# board2eco.net
KiCad netlist of a schematic drawn in EAGLE
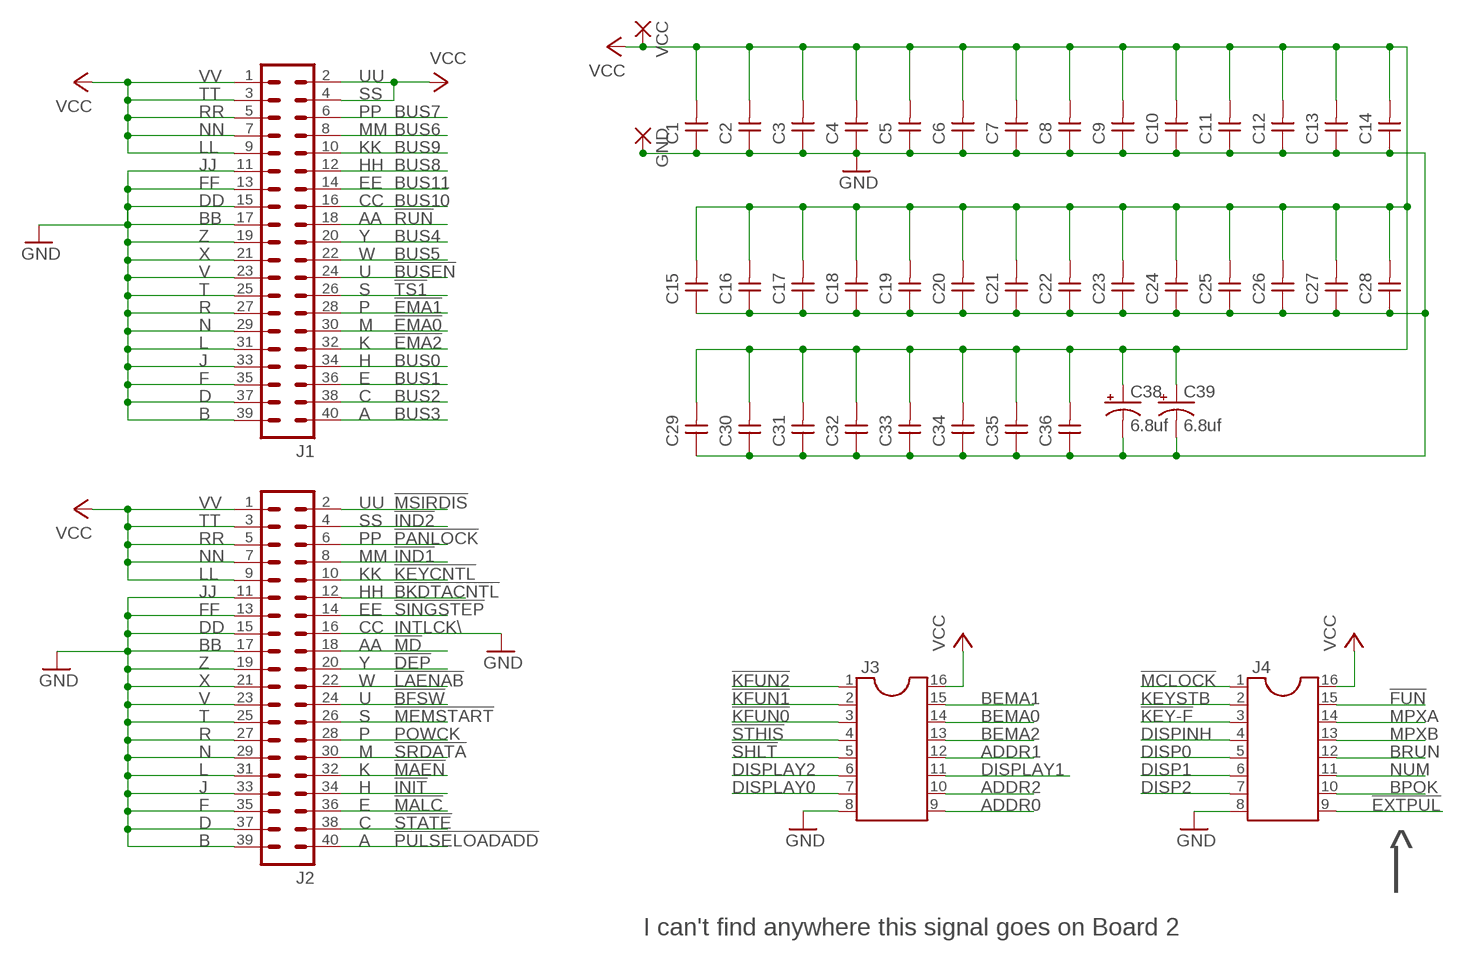
[diagram p0: schematic, sheet 1]
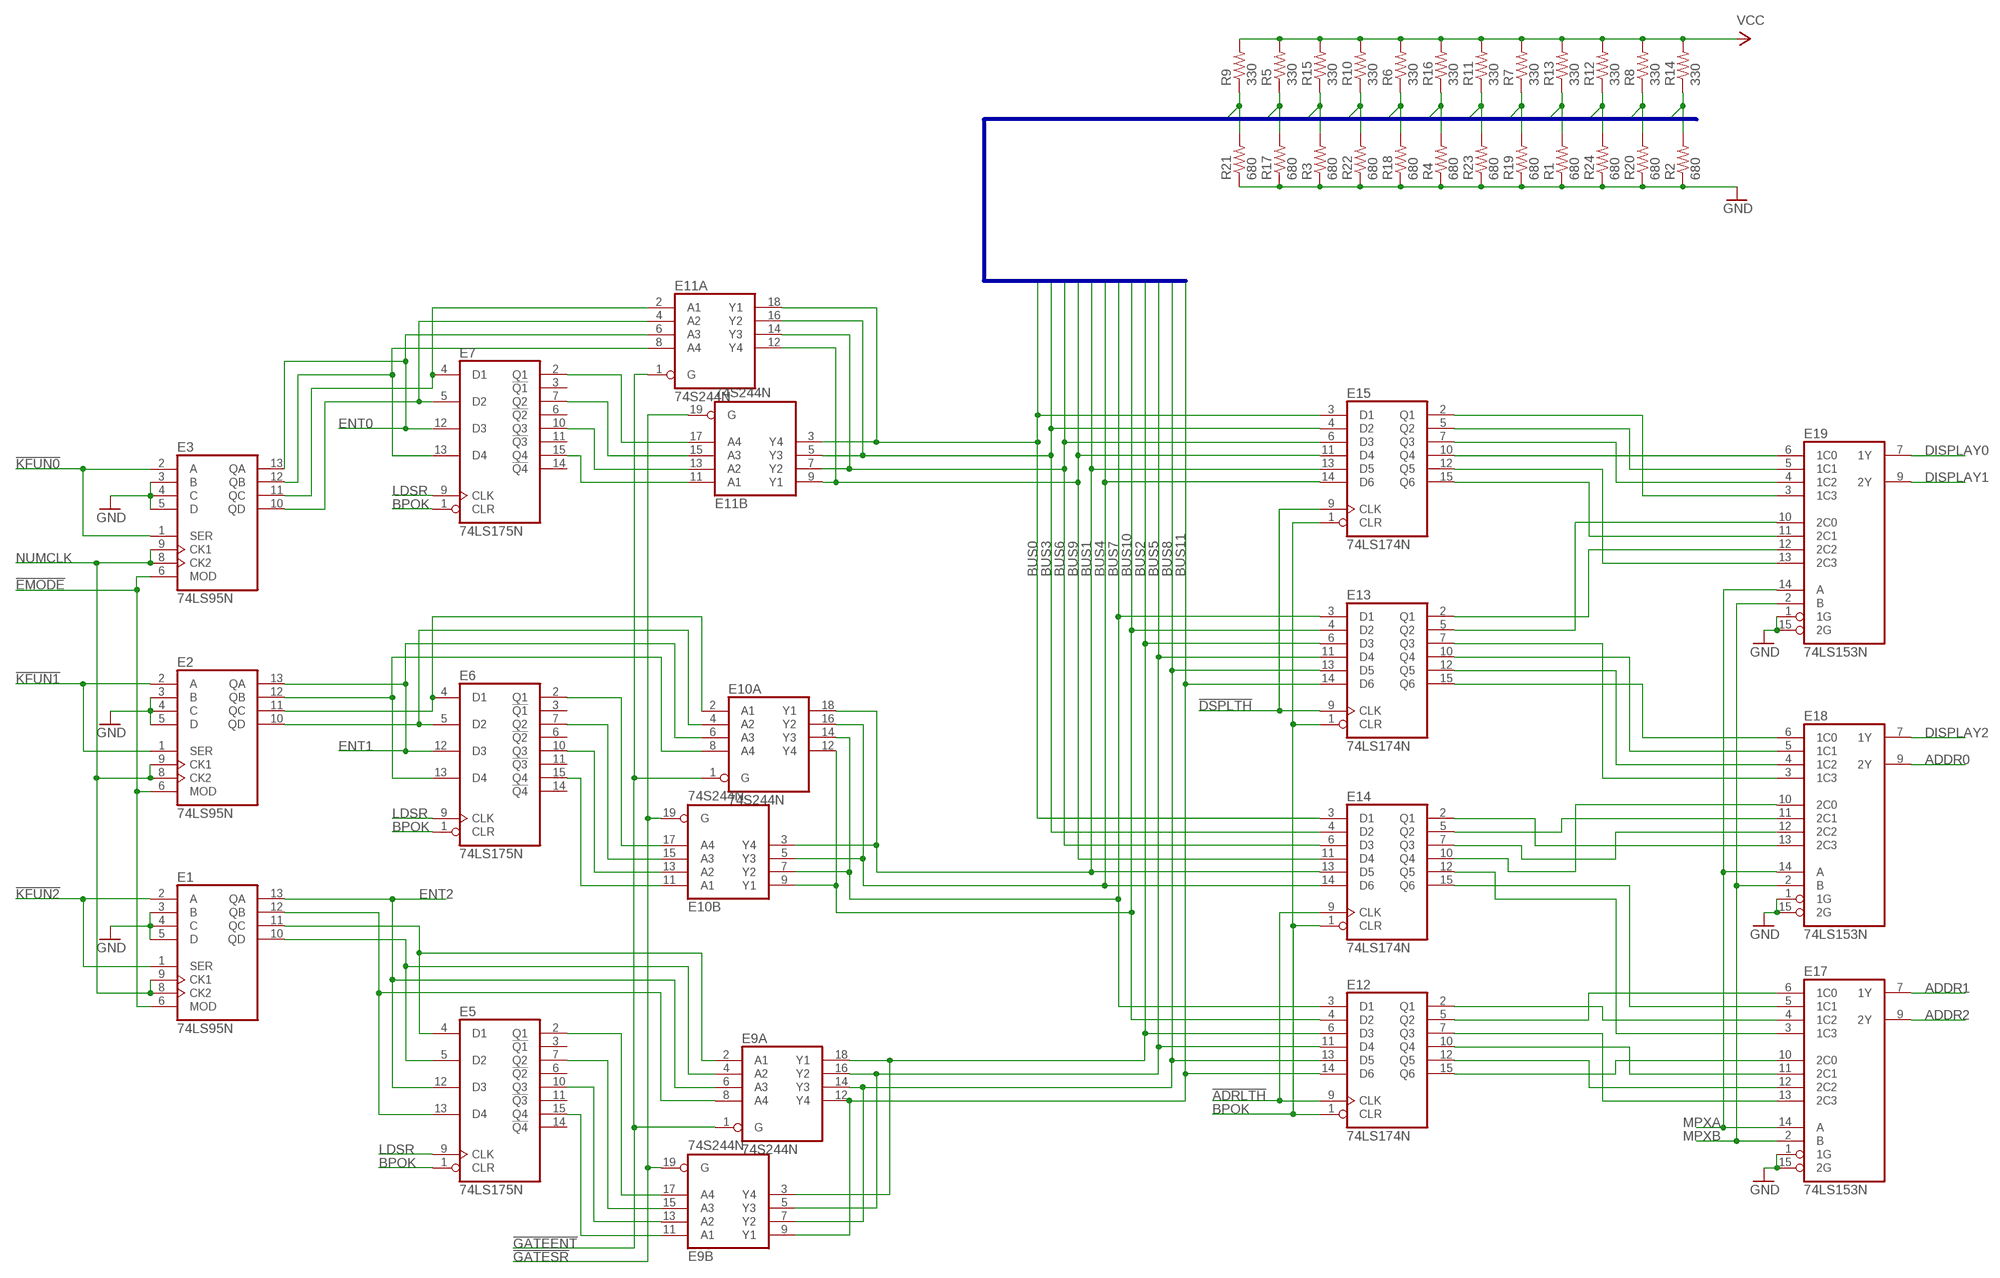
[diagram p1: schematic, sheet 2]
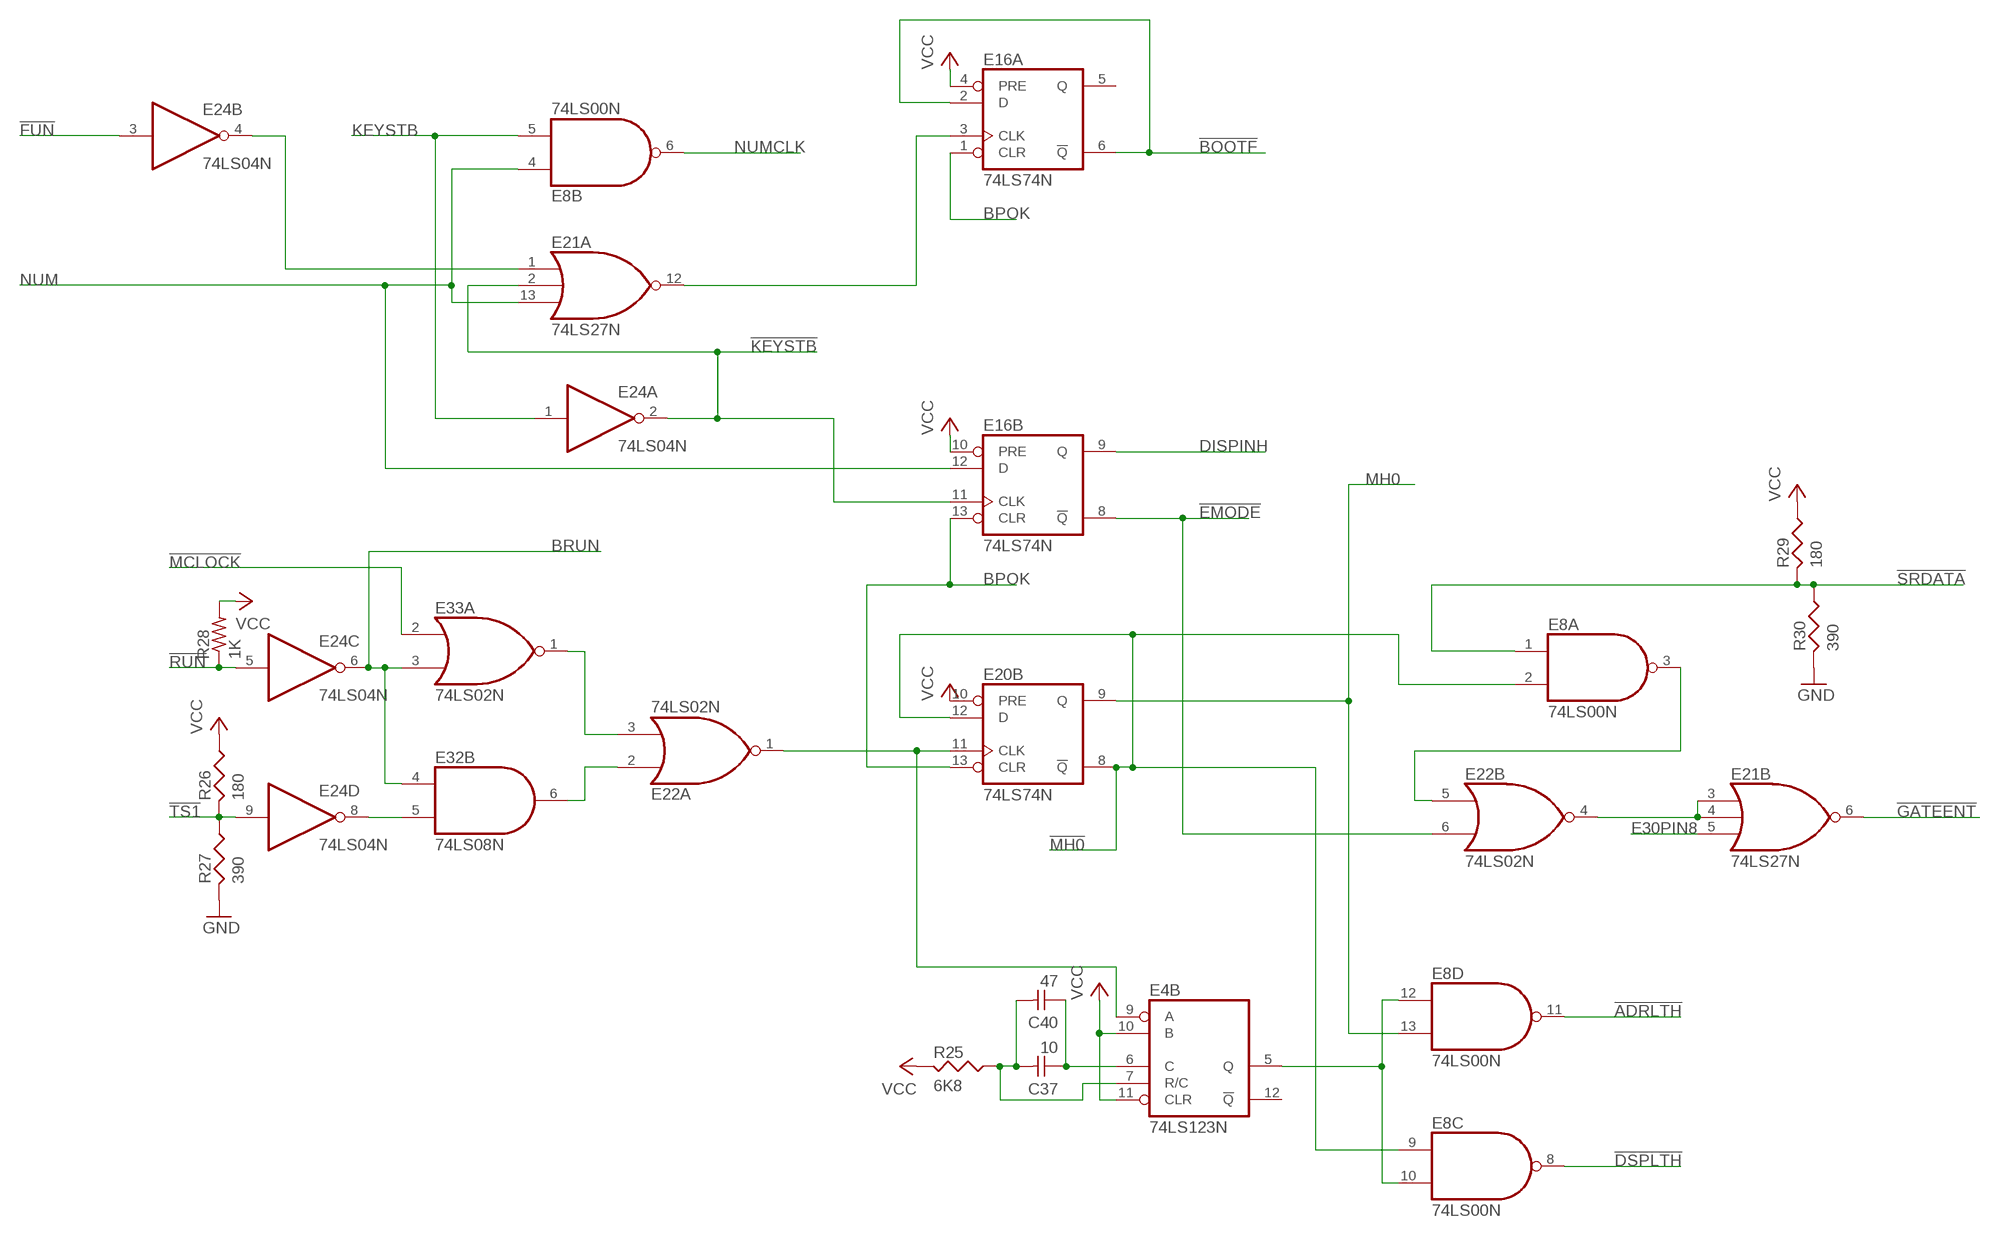
[diagram p2: schematic, sheet 3]
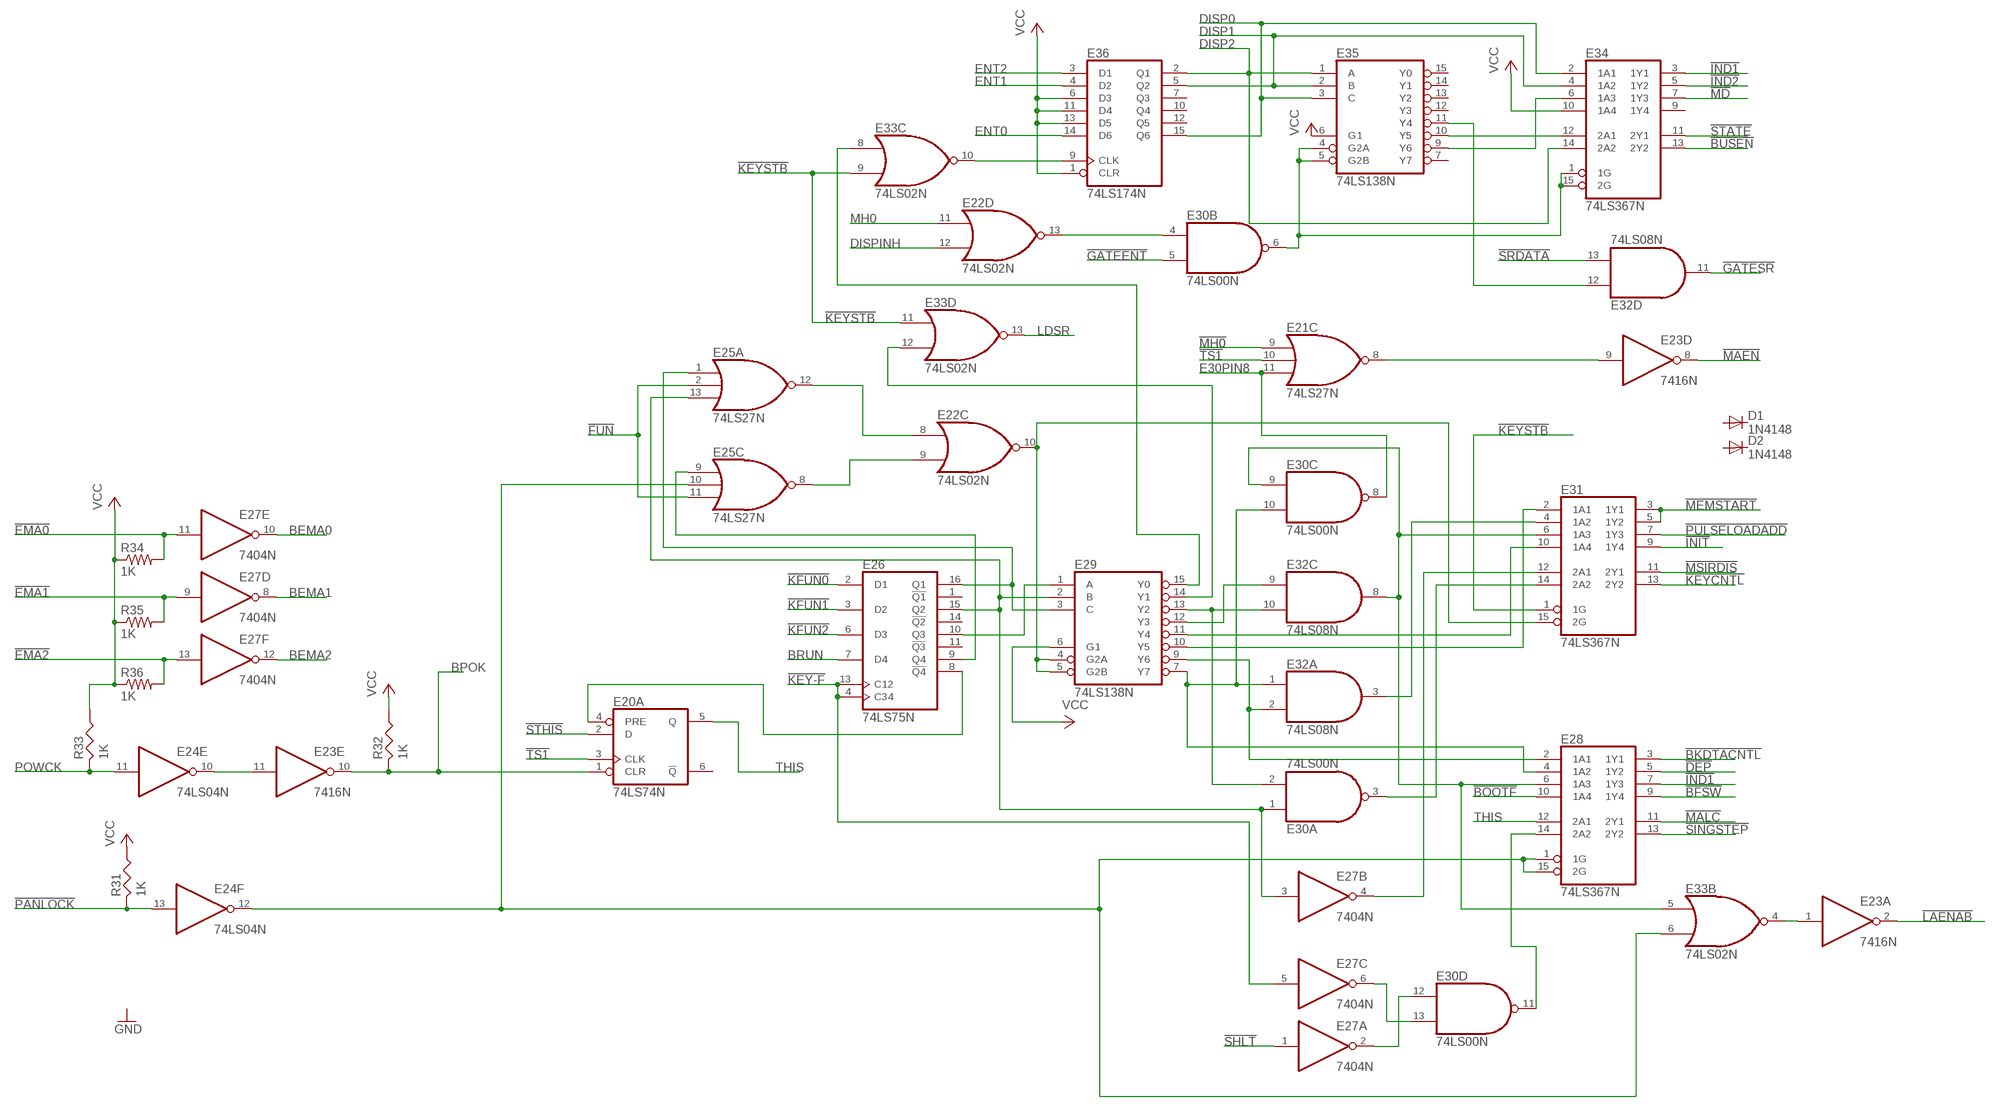
[diagram p3: schematic, sheet 4]

(export (version "E")
  (design (tool "Eeschema 10.0.6"))
  (components
    (comp (ref "E1")
      (value "74LS95N")
      (footprint "eagle-import:DIL14")
      (libsource (lib "eagle-import") (part "7495NLS"))
    )
    (comp (ref "E2")
      (value "74LS95N")
      (footprint "eagle-import:DIL14")
      (libsource (lib "eagle-import") (part "7495NLS"))
    )
    (comp (ref "E3")
      (value "74LS95N")
      (footprint "eagle-import:DIL14")
      (libsource (lib "eagle-import") (part "7495NLS"))
    )
    (comp (ref "E5")
      (value "74LS175N")
      (footprint "eagle-import:DIL16")
      (libsource (lib "eagle-import") (part "74175NLS"))
    )
    (comp (ref "E6")
      (value "74LS175N")
      (footprint "eagle-import:DIL16")
      (libsource (lib "eagle-import") (part "74175NLS"))
    )
    (comp (ref "E7")
      (value "74LS175N")
      (footprint "eagle-import:DIL16")
      (libsource (lib "eagle-import") (part "74175NLS"))
    )
    (comp (ref "E9")
      (value "74S244N")
      (footprint "eagle-import:DIL20")
      (libsource (lib "eagle-import") (part "74244NS"))
    )
    (comp (ref "E10")
      (value "74S244N")
      (footprint "eagle-import:DIL20")
      (libsource (lib "eagle-import") (part "74244NS"))
    )
    (comp (ref "E11")
      (value "74S244N")
      (footprint "eagle-import:DIL20")
      (libsource (lib "eagle-import") (part "74244NS"))
    )
    (comp (ref "E12")
      (value "74LS174N")
      (footprint "eagle-import:DIL16")
      (libsource (lib "eagle-import") (part "74174NLS"))
    )
    (comp (ref "E13")
      (value "74LS174N")
      (footprint "eagle-import:DIL16")
      (libsource (lib "eagle-import") (part "74174NLS"))
    )
    (comp (ref "E14")
      (value "74LS174N")
      (footprint "eagle-import:DIL16")
      (libsource (lib "eagle-import") (part "74174NLS"))
    )
    (comp (ref "E15")
      (value "74LS174N")
      (footprint "eagle-import:DIL16")
      (libsource (lib "eagle-import") (part "74174NLS"))
    )
    (comp (ref "E17")
      (value "74LS153N")
      (footprint "eagle-import:DIL16")
      (libsource (lib "eagle-import") (part "74153NLS"))
    )
    (comp (ref "E18")
      (value "74LS153N")
      (footprint "eagle-import:DIL16")
      (libsource (lib "eagle-import") (part "74153NLS"))
    )
    (comp (ref "E19")
      (value "74LS153N")
      (footprint "eagle-import:DIL16")
      (libsource (lib "eagle-import") (part "74153NLS"))
    )
    (comp (ref "R1")
      (value "680")
      (footprint "eagle-import:0207_10")
      (libsource (lib "eagle-import") (part "R-US_0207/10"))
    )
    (comp (ref "R2")
      (value "680")
      (footprint "eagle-import:0207_10")
      (libsource (lib "eagle-import") (part "R-US_0207/10"))
    )
    (comp (ref "R3")
      (value "680")
      (footprint "eagle-import:0207_10")
      (libsource (lib "eagle-import") (part "R-US_0207/10"))
    )
    (comp (ref "R4")
      (value "680")
      (footprint "eagle-import:0207_10")
      (libsource (lib "eagle-import") (part "R-US_0207/10"))
    )
    (comp (ref "R5")
      (value "330")
      (footprint "eagle-import:0207_10")
      (libsource (lib "eagle-import") (part "R-US_0207/10"))
    )
    (comp (ref "R6")
      (value "330")
      (footprint "eagle-import:0207_10")
      (libsource (lib "eagle-import") (part "R-US_0207/10"))
    )
    (comp (ref "R7")
      (value "330")
      (footprint "eagle-import:0207_10")
      (libsource (lib "eagle-import") (part "R-US_0207/10"))
    )
    (comp (ref "R8")
      (value "330")
      (footprint "eagle-import:0207_10")
      (libsource (lib "eagle-import") (part "R-US_0207/10"))
    )
    (comp (ref "R9")
      (value "330")
      (footprint "eagle-import:0207_10")
      (libsource (lib "eagle-import") (part "R-US_0207/10"))
    )
    (comp (ref "R10")
      (value "330")
      (footprint "eagle-import:0207_10")
      (libsource (lib "eagle-import") (part "R-US_0207/10"))
    )
    (comp (ref "R11")
      (value "330")
      (footprint "eagle-import:0207_10")
      (libsource (lib "eagle-import") (part "R-US_0207/10"))
    )
    (comp (ref "R12")
      (value "330")
      (footprint "eagle-import:0207_10")
      (libsource (lib "eagle-import") (part "R-US_0207/10"))
    )
    (comp (ref "R13")
      (value "330")
      (footprint "eagle-import:0207_10")
      (libsource (lib "eagle-import") (part "R-US_0207/10"))
    )
    (comp (ref "R14")
      (value "330")
      (footprint "eagle-import:0207_10")
      (libsource (lib "eagle-import") (part "R-US_0207/10"))
    )
    (comp (ref "R15")
      (value "330")
      (footprint "eagle-import:0207_10")
      (libsource (lib "eagle-import") (part "R-US_0207/10"))
    )
    (comp (ref "R16")
      (value "330")
      (footprint "eagle-import:0207_10")
      (libsource (lib "eagle-import") (part "R-US_0207/10"))
    )
    (comp (ref "R17")
      (value "680")
      (footprint "eagle-import:0207_10")
      (libsource (lib "eagle-import") (part "R-US_0207/10"))
    )
    (comp (ref "R18")
      (value "680")
      (footprint "eagle-import:0207_10")
      (libsource (lib "eagle-import") (part "R-US_0207/10"))
    )
    (comp (ref "R19")
      (value "680")
      (footprint "eagle-import:0207_10")
      (libsource (lib "eagle-import") (part "R-US_0207/10"))
    )
    (comp (ref "R20")
      (value "680")
      (footprint "eagle-import:0207_10")
      (libsource (lib "eagle-import") (part "R-US_0207/10"))
    )
    (comp (ref "R21")
      (value "680")
      (footprint "eagle-import:0207_10")
      (libsource (lib "eagle-import") (part "R-US_0207/10"))
    )
    (comp (ref "R22")
      (value "680")
      (footprint "eagle-import:0207_10")
      (libsource (lib "eagle-import") (part "R-US_0207/10"))
    )
    (comp (ref "R23")
      (value "680")
      (footprint "eagle-import:0207_10")
      (libsource (lib "eagle-import") (part "R-US_0207/10"))
    )
    (comp (ref "R24")
      (value "680")
      (footprint "eagle-import:0207_10")
      (libsource (lib "eagle-import") (part "R-US_0207/10"))
    )
    (comp (ref "C37")
      (value "10")
      (footprint "eagle-import:C-5")
      (libsource (lib "eagle-import") (part "CAPNP-5"))
    )
    (comp (ref "C40")
      (value "47")
      (footprint "eagle-import:C-5")
      (libsource (lib "eagle-import") (part "CAPNP-5"))
    )
    (comp (ref "E4")
      (value "74LS123N")
      (footprint "eagle-import:DIL16")
      (libsource (lib "eagle-import") (part "74123NLS"))
    )
    (comp (ref "E8")
      (value "74LS00N")
      (footprint "eagle-import:DIL14")
      (libsource (lib "eagle-import") (part "7400NLS"))
    )
    (comp (ref "E16")
      (value "74LS74N")
      (footprint "eagle-import:DIL14")
      (libsource (lib "eagle-import") (part "7474NLS"))
    )
    (comp (ref "E20")
      (value "74LS74N")
      (footprint "eagle-import:DIL14")
      (libsource (lib "eagle-import") (part "7474NLS"))
    )
    (comp (ref "E21")
      (value "74LS27N")
      (footprint "eagle-import:DIL14")
      (libsource (lib "eagle-import") (part "7427NLS"))
    )
    (comp (ref "E22")
      (value "74LS02N")
      (footprint "eagle-import:DIL14")
      (libsource (lib "eagle-import") (part "7402NLS"))
    )
    (comp (ref "E24")
      (value "74LS04N")
      (footprint "eagle-import:DIL14")
      (libsource (lib "eagle-import") (part "7404NLS"))
    )
    (comp (ref "E32")
      (value "74LS08N")
      (footprint "eagle-import:DIL14")
      (libsource (lib "eagle-import") (part "7408NLS"))
    )
    (comp (ref "E33")
      (value "74LS02N")
      (footprint "eagle-import:DIL14")
      (libsource (lib "eagle-import") (part "7402NLS"))
    )
    (comp (ref "R25")
      (value "6K8")
      (footprint "eagle-import:R-10")
      (libsource (lib "eagle-import") (part "RESUS-10"))
    )
    (comp (ref "R26")
      (value "180")
      (footprint "eagle-import:R-10")
      (libsource (lib "eagle-import") (part "RESUS-10"))
    )
    (comp (ref "R27")
      (value "390")
      (footprint "eagle-import:R-10")
      (libsource (lib "eagle-import") (part "RESUS-10"))
    )
    (comp (ref "R28")
      (value "1K")
      (footprint "eagle-import:0207_10")
      (libsource (lib "eagle-import") (part "R-US_0207/10"))
    )
    (comp (ref "R29")
      (value "180")
      (footprint "eagle-import:R-10")
      (libsource (lib "eagle-import") (part "RESUS-10"))
    )
    (comp (ref "R30")
      (value "390")
      (footprint "eagle-import:R-10")
      (libsource (lib "eagle-import") (part "RESUS-10"))
    )
    (comp (ref "D1")
      (value "1N4148")
      (footprint "eagle-import:DO35-10")
      (libsource (lib "eagle-import") (part "1N4148"))
    )
    (comp (ref "D2")
      (value "1N4148")
      (footprint "eagle-import:DO35-10")
      (libsource (lib "eagle-import") (part "1N4148"))
    )
    (comp (ref "E23")
      (value "7416N")
      (footprint "eagle-import:DIL14")
      (libsource (lib "eagle-import") (part "7416N"))
    )
    (comp (ref "E25")
      (value "74LS27N")
      (footprint "eagle-import:DIL14")
      (libsource (lib "eagle-import") (part "7427NLS"))
    )
    (comp (ref "E26")
      (value "74LS75N")
      (footprint "eagle-import:DIL16")
      (libsource (lib "eagle-import") (part "7475NLS"))
    )
    (comp (ref "E27")
      (value "7404N")
      (footprint "eagle-import:DIL14")
      (libsource (lib "eagle-import") (part "7404N"))
    )
    (comp (ref "E28")
      (value "74LS367N")
      (footprint "eagle-import:DIL16")
      (libsource (lib "eagle-import") (part "74367N"))
    )
    (comp (ref "E29")
      (value "74LS138N")
      (footprint "eagle-import:DIL16")
      (libsource (lib "eagle-import") (part "74138NLS"))
    )
    (comp (ref "E30")
      (value "74LS00N")
      (footprint "eagle-import:DIL14")
      (libsource (lib "eagle-import") (part "7400NLS"))
    )
    (comp (ref "E31")
      (value "74LS367N")
      (footprint "eagle-import:DIL16")
      (libsource (lib "eagle-import") (part "74367N"))
    )
    (comp (ref "E34")
      (value "74LS367N")
      (footprint "eagle-import:DIL16")
      (libsource (lib "eagle-import") (part "74367N"))
    )
    (comp (ref "E35")
      (value "74LS138N")
      (footprint "eagle-import:DIL16")
      (libsource (lib "eagle-import") (part "74138NLS"))
    )
    (comp (ref "E36")
      (value "74LS174N")
      (footprint "eagle-import:DIL16")
      (libsource (lib "eagle-import") (part "74174NLS"))
    )
    (comp (ref "R31")
      (value "1K")
      (footprint "eagle-import:R-10")
      (libsource (lib "eagle-import") (part "RESUS-10"))
    )
    (comp (ref "R32")
      (value "1K")
      (footprint "eagle-import:R-10")
      (libsource (lib "eagle-import") (part "RESUS-10"))
    )
    (comp (ref "R33")
      (value "1K")
      (footprint "eagle-import:R-10")
      (libsource (lib "eagle-import") (part "RESUS-10"))
    )
    (comp (ref "R34")
      (value "1K")
      (footprint "eagle-import:0207_10")
      (libsource (lib "eagle-import") (part "R-US_0207/10"))
    )
    (comp (ref "R35")
      (value "1K")
      (footprint "eagle-import:0207_10")
      (libsource (lib "eagle-import") (part "R-US_0207/10"))
    )
    (comp (ref "R36")
      (value "1K")
      (footprint "eagle-import:0207_10")
      (libsource (lib "eagle-import") (part "R-US_0207/10"))
    )
    (comp (ref "C1")
      (value "CAPNP-5")
      (footprint "eagle-import:C-5")
      (libsource (lib "eagle-import") (part "CAPNP-5"))
    )
    (comp (ref "C2")
      (value "CAPNP-5")
      (footprint "eagle-import:C-5")
      (libsource (lib "eagle-import") (part "CAPNP-5"))
    )
    (comp (ref "C3")
      (value "CAPNP-5")
      (footprint "eagle-import:C-5")
      (libsource (lib "eagle-import") (part "CAPNP-5"))
    )
    (comp (ref "C4")
      (value "CAPNP-5")
      (footprint "eagle-import:C-5")
      (libsource (lib "eagle-import") (part "CAPNP-5"))
    )
    (comp (ref "C5")
      (value "CAPNP-5")
      (footprint "eagle-import:C-5")
      (libsource (lib "eagle-import") (part "CAPNP-5"))
    )
    (comp (ref "C6")
      (value "CAPNP-5")
      (footprint "eagle-import:C-5")
      (libsource (lib "eagle-import") (part "CAPNP-5"))
    )
    (comp (ref "C7")
      (value "CAPNP-5")
      (footprint "eagle-import:C-5")
      (libsource (lib "eagle-import") (part "CAPNP-5"))
    )
    (comp (ref "C8")
      (value "CAPNP-5")
      (footprint "eagle-import:C-5")
      (libsource (lib "eagle-import") (part "CAPNP-5"))
    )
    (comp (ref "C9")
      (value "CAPNP-5")
      (footprint "eagle-import:C-5")
      (libsource (lib "eagle-import") (part "CAPNP-5"))
    )
    (comp (ref "C10")
      (value "CAPNP-5")
      (footprint "eagle-import:C-5")
      (libsource (lib "eagle-import") (part "CAPNP-5"))
    )
    (comp (ref "C11")
      (value "CAPNP-5")
      (footprint "eagle-import:C-5")
      (libsource (lib "eagle-import") (part "CAPNP-5"))
    )
    (comp (ref "C12")
      (value "CAPNP-5")
      (footprint "eagle-import:C-5")
      (libsource (lib "eagle-import") (part "CAPNP-5"))
    )
    (comp (ref "C13")
      (value "CAPNP-5")
      (footprint "eagle-import:C-5")
      (libsource (lib "eagle-import") (part "CAPNP-5"))
    )
    (comp (ref "C14")
      (value "CAPNP-5")
      (footprint "eagle-import:C-5")
      (libsource (lib "eagle-import") (part "CAPNP-5"))
    )
    (comp (ref "C15")
      (value "CAPNP-5")
      (footprint "eagle-import:C-5")
      (libsource (lib "eagle-import") (part "CAPNP-5"))
    )
    (comp (ref "C16")
      (value "CAPNP-5")
      (footprint "eagle-import:C-5")
      (libsource (lib "eagle-import") (part "CAPNP-5"))
    )
    (comp (ref "C17")
      (value "CAPNP-5")
      (footprint "eagle-import:C-5")
      (libsource (lib "eagle-import") (part "CAPNP-5"))
    )
    (comp (ref "C18")
      (value "CAPNP-5")
      (footprint "eagle-import:C-5")
      (libsource (lib "eagle-import") (part "CAPNP-5"))
    )
    (comp (ref "C19")
      (value "CAPNP-5")
      (footprint "eagle-import:C-5")
      (libsource (lib "eagle-import") (part "CAPNP-5"))
    )
    (comp (ref "C20")
      (value "CAPNP-5")
      (footprint "eagle-import:C-5")
      (libsource (lib "eagle-import") (part "CAPNP-5"))
    )
    (comp (ref "C21")
      (value "CAPNP-5")
      (footprint "eagle-import:C-5")
      (libsource (lib "eagle-import") (part "CAPNP-5"))
    )
    (comp (ref "C22")
      (value "CAPNP-5")
      (footprint "eagle-import:C-5")
      (libsource (lib "eagle-import") (part "CAPNP-5"))
    )
    (comp (ref "C23")
      (value "CAPNP-5")
      (footprint "eagle-import:C-5")
      (libsource (lib "eagle-import") (part "CAPNP-5"))
    )
    (comp (ref "C24")
      (value "CAPNP-5")
      (footprint "eagle-import:C-5")
      (libsource (lib "eagle-import") (part "CAPNP-5"))
    )
    (comp (ref "C25")
      (value "CAPNP-5")
      (footprint "eagle-import:C-5")
      (libsource (lib "eagle-import") (part "CAPNP-5"))
    )
    (comp (ref "C26")
      (value "CAPNP-5")
      (footprint "eagle-import:C-5")
      (libsource (lib "eagle-import") (part "CAPNP-5"))
    )
    (comp (ref "C27")
      (value "CAPNP-5")
      (footprint "eagle-import:C-5")
      (libsource (lib "eagle-import") (part "CAPNP-5"))
    )
    (comp (ref "C28")
      (value "CAPNP-5")
      (footprint "eagle-import:C-5")
      (libsource (lib "eagle-import") (part "CAPNP-5"))
    )
    (comp (ref "C29")
      (value "CAPNP-5")
      (footprint "eagle-import:C-5")
      (libsource (lib "eagle-import") (part "CAPNP-5"))
    )
    (comp (ref "C30")
      (value "CAPNP-5")
      (footprint "eagle-import:C-5")
      (libsource (lib "eagle-import") (part "CAPNP-5"))
    )
    (comp (ref "C31")
      (value "CAPNP-5")
      (footprint "eagle-import:C-5")
      (libsource (lib "eagle-import") (part "CAPNP-5"))
    )
    (comp (ref "C32")
      (value "CAPNP-5")
      (footprint "eagle-import:C-5")
      (libsource (lib "eagle-import") (part "CAPNP-5"))
    )
    (comp (ref "C33")
      (value "CAPNP-5")
      (footprint "eagle-import:C-5")
      (libsource (lib "eagle-import") (part "CAPNP-5"))
    )
    (comp (ref "C34")
      (value "CAPNP-5")
      (footprint "eagle-import:C-5")
      (libsource (lib "eagle-import") (part "CAPNP-5"))
    )
    (comp (ref "C35")
      (value "CAPNP-5")
      (footprint "eagle-import:C-5")
      (libsource (lib "eagle-import") (part "CAPNP-5"))
    )
    (comp (ref "C36")
      (value "CAPNP-5")
      (footprint "eagle-import:C-5")
      (libsource (lib "eagle-import") (part "CAPNP-5"))
    )
    (comp (ref "C38")
      (value "6.8uf")
      (footprint "eagle-import:E15-5")
      (libsource (lib "eagle-import") (part "CPOL-USE15-5AXIAL"))
    )
    (comp (ref "C39")
      (value "6.8uf")
      (footprint "eagle-import:E15-5")
      (libsource (lib "eagle-import") (part "CPOL-USE15-5AXIAL"))
    )
    (comp (ref "GND")
      (value "3,81/1,4")
      (footprint "eagle-import:3,81_1,4")
      (libsource (lib "eagle-import") (part "3,81/1,4"))
    )
    (comp (ref "J1")
      (value "40H")
      (footprint "eagle-import:40H")
      (libsource (lib "eagle-import") (part "40H"))
    )
    (comp (ref "J2")
      (value "40H")
      (footprint "eagle-import:40H")
      (libsource (lib "eagle-import") (part "40H"))
    )
    (comp (ref "J3")
      (value "DIL16S")
      (footprint "eagle-import:SOCKED-16")
      (libsource (lib "eagle-import") (part "DIL16S"))
    )
    (comp (ref "J4")
      (value "DIL16S")
      (footprint "eagle-import:SOCKED-16")
      (libsource (lib "eagle-import") (part "DIL16S"))
    )
    (comp (ref "VCC")
      (value "3,81/1,4")
      (footprint "eagle-import:3,81_1,4")
      (libsource (lib "eagle-import") (part "3,81/1,4"))
    )
  )
  (nets
    (net (code "1") (name "ADDR0") (class "Default")
      (node (ref "E18") (pin "9") (pinfunction "2Y_9") (pintype "output"))
      (node (ref "J3") (pin "9") (pinfunction "9_9") (pintype "passive"))
    )
    (net (code "2") (name "ADDR1") (class "Default")
      (node (ref "E17") (pin "7") (pinfunction "1Y_7") (pintype "output"))
      (node (ref "J3") (pin "12") (pinfunction "12_12") (pintype "passive"))
    )
    (net (code "3") (name "ADDR2") (class "Default")
      (node (ref "E17") (pin "9") (pinfunction "2Y_9") (pintype "output"))
      (node (ref "J3") (pin "10") (pinfunction "10_10") (pintype "passive"))
    )
    (net (code "4") (name "BEMA0") (class "Default")
      (node (ref "E27") (pin "10") (pinfunction "O_10") (pintype "output"))
      (node (ref "J3") (pin "14") (pinfunction "14_14") (pintype "passive"))
    )
    (net (code "5") (name "BEMA1") (class "Default")
      (node (ref "E27") (pin "8") (pinfunction "O_8") (pintype "output"))
      (node (ref "J3") (pin "15") (pinfunction "15_15") (pintype "passive"))
    )
    (net (code "6") (name "BEMA2") (class "Default")
      (node (ref "E27") (pin "12") (pinfunction "O_12") (pintype "output"))
      (node (ref "J3") (pin "13") (pinfunction "13_13") (pintype "passive"))
    )
    (net (code "7") (name "BPOK") (class "Default")
      (node (ref "E12") (pin "1") (pinfunction "CLR_1") (pintype "input"))
      (node (ref "E13") (pin "1") (pinfunction "CLR_1") (pintype "input"))
      (node (ref "E14") (pin "1") (pinfunction "CLR_1") (pintype "input"))
      (node (ref "E15") (pin "1") (pinfunction "CLR_1") (pintype "input"))
      (node (ref "E16") (pin "1") (pinfunction "CLR_1") (pintype "input"))
      (node (ref "E16") (pin "13") (pinfunction "CLR_13") (pintype "input"))
      (node (ref "E20") (pin "1") (pinfunction "CLR_1") (pintype "input"))
      (node (ref "E20") (pin "13") (pinfunction "CLR_13") (pintype "input"))
      (node (ref "E23") (pin "10") (pinfunction "O_10") (pintype "open_collector"))
      (node (ref "E5") (pin "1") (pinfunction "CLR_1") (pintype "input"))
      (node (ref "E6") (pin "1") (pinfunction "CLR_1") (pintype "input"))
      (node (ref "E7") (pin "1") (pinfunction "CLR_1") (pintype "input"))
      (node (ref "J4") (pin "10") (pinfunction "10_10") (pintype "passive"))
      (node (ref "R32") (pin "2") (pinfunction "2_2") (pintype "passive"))
    )
    (net (code "8") (name "BRUN") (class "Default")
      (node (ref "E24") (pin "6") (pinfunction "O_6") (pintype "output"))
      (node (ref "E26") (pin "7") (pinfunction "D4_7") (pintype "input"))
      (node (ref "E32") (pin "4") (pinfunction "I0_4") (pintype "input"))
      (node (ref "E33") (pin "3") (pinfunction "I1_3") (pintype "input"))
      (node (ref "J4") (pin "12") (pinfunction "12_12") (pintype "passive"))
    )
    (net (code "9") (name "BUS0") (class "Default")
      (node (ref "E11") (pin "18") (pinfunction "Y1_18") (pintype "tri_state"))
      (node (ref "E11") (pin "3") (pinfunction "Y4_3") (pintype "tri_state"))
      (node (ref "E14") (pin "3") (pinfunction "D1_3") (pintype "input"))
      (node (ref "E15") (pin "3") (pinfunction "D1_3") (pintype "input"))
      (node (ref "J1") (pin "34") (pinfunction "34_34") (pintype "passive"))
      (node (ref "R21") (pin "2") (pinfunction "2_2") (pintype "passive"))
      (node (ref "R9") (pin "1") (pinfunction "1_1") (pintype "passive"))
    )
    (net (code "10") (name "BUS1") (class "Default")
      (node (ref "E10") (pin "18") (pinfunction "Y1_18") (pintype "tri_state"))
      (node (ref "E10") (pin "3") (pinfunction "Y4_3") (pintype "tri_state"))
      (node (ref "E14") (pin "13") (pinfunction "D5_13") (pintype "input"))
      (node (ref "E15") (pin "13") (pinfunction "D5_13") (pintype "input"))
      (node (ref "J1") (pin "36") (pinfunction "36_36") (pintype "passive"))
      (node (ref "R17") (pin "2") (pinfunction "2_2") (pintype "passive"))
      (node (ref "R5") (pin "1") (pinfunction "1_1") (pintype "passive"))
    )
    (net (code "11") (name "BUS2") (class "Default")
      (node (ref "E12") (pin "6") (pinfunction "D3_6") (pintype "input"))
      (node (ref "E13") (pin "6") (pinfunction "D3_6") (pintype "input"))
      (node (ref "E9") (pin "18") (pinfunction "Y1_18") (pintype "tri_state"))
      (node (ref "E9") (pin "3") (pinfunction "Y4_3") (pintype "tri_state"))
      (node (ref "J1") (pin "38") (pinfunction "38_38") (pintype "passive"))
      (node (ref "R15") (pin "1") (pinfunction "1_1") (pintype "passive"))
      (node (ref "R3") (pin "2") (pinfunction "2_2") (pintype "passive"))
    )
    (net (code "12") (name "BUS3") (class "Default")
      (node (ref "E11") (pin "16") (pinfunction "Y2_16") (pintype "tri_state"))
      (node (ref "E11") (pin "5") (pinfunction "Y3_5") (pintype "tri_state"))
      (node (ref "E14") (pin "4") (pinfunction "D2_4") (pintype "input"))
      (node (ref "E15") (pin "4") (pinfunction "D2_4") (pintype "input"))
      (node (ref "J1") (pin "40") (pinfunction "40_40") (pintype "passive"))
      (node (ref "R10") (pin "1") (pinfunction "1_1") (pintype "passive"))
      (node (ref "R22") (pin "2") (pinfunction "2_2") (pintype "passive"))
    )
    (net (code "13") (name "BUS4") (class "Default")
      (node (ref "E10") (pin "16") (pinfunction "Y2_16") (pintype "tri_state"))
      (node (ref "E10") (pin "5") (pinfunction "Y3_5") (pintype "tri_state"))
      (node (ref "E14") (pin "14") (pinfunction "D6_14") (pintype "input"))
      (node (ref "E15") (pin "14") (pinfunction "D6_14") (pintype "input"))
      (node (ref "J1") (pin "20") (pinfunction "20_20") (pintype "passive"))
      (node (ref "R18") (pin "2") (pinfunction "2_2") (pintype "passive"))
      (node (ref "R6") (pin "1") (pinfunction "1_1") (pintype "passive"))
    )
    (net (code "14") (name "BUS5") (class "Default")
      (node (ref "E12") (pin "11") (pinfunction "D4_11") (pintype "input"))
      (node (ref "E13") (pin "11") (pinfunction "D4_11") (pintype "input"))
      (node (ref "E9") (pin "16") (pinfunction "Y2_16") (pintype "tri_state"))
      (node (ref "E9") (pin "5") (pinfunction "Y3_5") (pintype "tri_state"))
      (node (ref "J1") (pin "22") (pinfunction "22_22") (pintype "passive"))
      (node (ref "R16") (pin "1") (pinfunction "1_1") (pintype "passive"))
      (node (ref "R4") (pin "2") (pinfunction "2_2") (pintype "passive"))
    )
    (net (code "15") (name "BUS6") (class "Default")
      (node (ref "E11") (pin "14") (pinfunction "Y3_14") (pintype "tri_state"))
      (node (ref "E11") (pin "7") (pinfunction "Y2_7") (pintype "tri_state"))
      (node (ref "E14") (pin "6") (pinfunction "D3_6") (pintype "input"))
      (node (ref "E15") (pin "6") (pinfunction "D3_6") (pintype "input"))
      (node (ref "J1") (pin "8") (pinfunction "8_8") (pintype "passive"))
      (node (ref "R11") (pin "1") (pinfunction "1_1") (pintype "passive"))
      (node (ref "R23") (pin "2") (pinfunction "2_2") (pintype "passive"))
    )
    (net (code "16") (name "BUS7") (class "Default")
      (node (ref "E10") (pin "14") (pinfunction "Y3_14") (pintype "tri_state"))
      (node (ref "E10") (pin "7") (pinfunction "Y2_7") (pintype "tri_state"))
      (node (ref "E12") (pin "3") (pinfunction "D1_3") (pintype "input"))
      (node (ref "E13") (pin "3") (pinfunction "D1_3") (pintype "input"))
      (node (ref "J1") (pin "6") (pinfunction "6_6") (pintype "passive"))
      (node (ref "R19") (pin "2") (pinfunction "2_2") (pintype "passive"))
      (node (ref "R7") (pin "1") (pinfunction "1_1") (pintype "passive"))
    )
    (net (code "17") (name "BUS8") (class "Default")
      (node (ref "E12") (pin "13") (pinfunction "D5_13") (pintype "input"))
      (node (ref "E13") (pin "13") (pinfunction "D5_13") (pintype "input"))
      (node (ref "E9") (pin "14") (pinfunction "Y3_14") (pintype "tri_state"))
      (node (ref "E9") (pin "7") (pinfunction "Y2_7") (pintype "tri_state"))
      (node (ref "J1") (pin "12") (pinfunction "12_12") (pintype "passive"))
      (node (ref "R1") (pin "2") (pinfunction "2_2") (pintype "passive"))
      (node (ref "R12") (pin "1") (pinfunction "1_1") (pintype "passive"))
      (node (ref "R13") (pin "1") (pinfunction "1_1") (pintype "passive"))
      (node (ref "R24") (pin "2") (pinfunction "2_2") (pintype "passive"))
    )
    (net (code "18") (name "BUS9") (class "Default")
      (node (ref "E11") (pin "12") (pinfunction "Y4_12") (pintype "tri_state"))
      (node (ref "E11") (pin "9") (pinfunction "Y1_9") (pintype "tri_state"))
      (node (ref "E14") (pin "11") (pinfunction "D4_11") (pintype "input"))
      (node (ref "E15") (pin "11") (pinfunction "D4_11") (pintype "input"))
      (node (ref "J1") (pin "10") (pinfunction "10_10") (pintype "passive"))
    )
    (net (code "19") (name "BUS10") (class "Default")
      (node (ref "E10") (pin "12") (pinfunction "Y4_12") (pintype "tri_state"))
      (node (ref "E10") (pin "9") (pinfunction "Y1_9") (pintype "tri_state"))
      (node (ref "E12") (pin "4") (pinfunction "D2_4") (pintype "input"))
      (node (ref "E13") (pin "4") (pinfunction "D2_4") (pintype "input"))
      (node (ref "J1") (pin "16") (pinfunction "16_16") (pintype "passive"))
      (node (ref "R20") (pin "2") (pinfunction "2_2") (pintype "passive"))
      (node (ref "R8") (pin "1") (pinfunction "1_1") (pintype "passive"))
    )
    (net (code "20") (name "BUS11") (class "Default")
      (node (ref "E12") (pin "14") (pinfunction "D6_14") (pintype "input"))
      (node (ref "E13") (pin "14") (pinfunction "D6_14") (pintype "input"))
      (node (ref "E9") (pin "12") (pinfunction "Y4_12") (pintype "tri_state"))
      (node (ref "E9") (pin "9") (pinfunction "Y1_9") (pintype "tri_state"))
      (node (ref "J1") (pin "14") (pinfunction "14_14") (pintype "passive"))
      (node (ref "R14") (pin "1") (pinfunction "1_1") (pintype "passive"))
      (node (ref "R2") (pin "2") (pinfunction "2_2") (pintype "passive"))
    )
    (net (code "21") (name "DISP0") (class "Default")
      (node (ref "E34") (pin "2") (pinfunction "1A1_2") (pintype "input"))
      (node (ref "E35") (pin "3") (pinfunction "C_3") (pintype "input"))
      (node (ref "E36") (pin "15") (pinfunction "Q6_15") (pintype "output"))
      (node (ref "J4") (pin "5") (pinfunction "5_5") (pintype "passive"))
    )
    (net (code "22") (name "DISP1") (class "Default")
      (node (ref "E34") (pin "4") (pinfunction "1A2_4") (pintype "input"))
      (node (ref "E35") (pin "2") (pinfunction "B_2") (pintype "input"))
      (node (ref "E36") (pin "5") (pinfunction "Q2_5") (pintype "output"))
      (node (ref "J4") (pin "6") (pinfunction "6_6") (pintype "passive"))
    )
    (net (code "23") (name "DISP2") (class "Default")
      (node (ref "E34") (pin "14") (pinfunction "2A2_14") (pintype "input"))
      (node (ref "E35") (pin "1") (pinfunction "A_1") (pintype "input"))
      (node (ref "E36") (pin "2") (pinfunction "Q1_2") (pintype "output"))
      (node (ref "J4") (pin "7") (pinfunction "7_7") (pintype "passive"))
    )
    (net (code "24") (name "DISPINH") (class "Default")
      (node (ref "E16") (pin "9") (pinfunction "Q_9") (pintype "output"))
      (node (ref "E22") (pin "12") (pinfunction "I1_12") (pintype "input"))
      (node (ref "J4") (pin "4") (pinfunction "4_4") (pintype "passive"))
    )
    (net (code "25") (name "DISPLAY0") (class "Default")
      (node (ref "E19") (pin "7") (pinfunction "1Y_7") (pintype "output"))
      (node (ref "J3") (pin "7") (pinfunction "7_7") (pintype "passive"))
    )
    (net (code "26") (name "DISPLAY1") (class "Default")
      (node (ref "E19") (pin "9") (pinfunction "2Y_9") (pintype "output"))
      (node (ref "J3") (pin "11") (pinfunction "11_11") (pintype "passive"))
    )
    (net (code "27") (name "DISPLAY2") (class "Default")
      (node (ref "E18") (pin "7") (pinfunction "1Y_7") (pintype "output"))
      (node (ref "J3") (pin "6") (pinfunction "6_6") (pintype "passive"))
    )
    (net (code "28") (name "E30PIN8") (class "Default")
      (node (ref "E21") (pin "11") (pinfunction "I2_11") (pintype "input"))
      (node (ref "E21") (pin "5") (pinfunction "I2_5") (pintype "input"))
      (node (ref "E30") (pin "8") (pinfunction "O_8") (pintype "output"))
    )
    (net (code "29") (name "ENT0") (class "Default")
      (node (ref "E11") (pin "6") (pinfunction "A3_6") (pintype "input"))
      (node (ref "E3") (pin "13") (pinfunction "QA_13") (pintype "output"))
      (node (ref "E36") (pin "14") (pinfunction "D6_14") (pintype "input"))
      (node (ref "E7") (pin "12") (pinfunction "D3_12") (pintype "input"))
    )
    (net (code "30") (name "ENT1") (class "Default")
      (node (ref "E10") (pin "6") (pinfunction "A3_6") (pintype "input"))
      (node (ref "E2") (pin "13") (pinfunction "QA_13") (pintype "output"))
      (node (ref "E36") (pin "4") (pinfunction "D2_4") (pintype "input"))
      (node (ref "E6") (pin "12") (pinfunction "D3_12") (pintype "input"))
    )
    (net (code "31") (name "ENT2") (class "Default")
      (node (ref "E1") (pin "13") (pinfunction "QA_13") (pintype "output"))
      (node (ref "E36") (pin "3") (pinfunction "D1_3") (pintype "input"))
      (node (ref "E5") (pin "12") (pinfunction "D3_12") (pintype "input"))
      (node (ref "E9") (pin "6") (pinfunction "A3_6") (pintype "input"))
    )
    (net (code "32") (name "GND") (class "Default")
      (node (ref "C1") (pin "1") (pinfunction "1_1") (pintype "passive"))
      (node (ref "C10") (pin "1") (pinfunction "1_1") (pintype "passive"))
      (node (ref "C11") (pin "1") (pinfunction "1_1") (pintype "passive"))
      (node (ref "C12") (pin "1") (pinfunction "1_1") (pintype "passive"))
      (node (ref "C13") (pin "1") (pinfunction "1_1") (pintype "passive"))
      (node (ref "C14") (pin "1") (pinfunction "1_1") (pintype "passive"))
      (node (ref "C15") (pin "1") (pinfunction "1_1") (pintype "passive"))
      (node (ref "C16") (pin "1") (pinfunction "1_1") (pintype "passive"))
      (node (ref "C17") (pin "1") (pinfunction "1_1") (pintype "passive"))
      (node (ref "C18") (pin "1") (pinfunction "1_1") (pintype "passive"))
      (node (ref "C19") (pin "1") (pinfunction "1_1") (pintype "passive"))
      (node (ref "C2") (pin "1") (pinfunction "1_1") (pintype "passive"))
      (node (ref "C20") (pin "1") (pinfunction "1_1") (pintype "passive"))
      (node (ref "C21") (pin "1") (pinfunction "1_1") (pintype "passive"))
      (node (ref "C22") (pin "1") (pinfunction "1_1") (pintype "passive"))
      (node (ref "C23") (pin "1") (pinfunction "1_1") (pintype "passive"))
      (node (ref "C24") (pin "1") (pinfunction "1_1") (pintype "passive"))
      (node (ref "C25") (pin "1") (pinfunction "1_1") (pintype "passive"))
      (node (ref "C26") (pin "1") (pinfunction "1_1") (pintype "passive"))
      (node (ref "C27") (pin "1") (pinfunction "1_1") (pintype "passive"))
      (node (ref "C28") (pin "1") (pinfunction "1_1") (pintype "passive"))
      (node (ref "C29") (pin "1") (pinfunction "1_1") (pintype "passive"))
      (node (ref "C3") (pin "1") (pinfunction "1_1") (pintype "passive"))
      (node (ref "C30") (pin "1") (pinfunction "1_1") (pintype "passive"))
      (node (ref "C31") (pin "1") (pinfunction "1_1") (pintype "passive"))
      (node (ref "C32") (pin "1") (pinfunction "1_1") (pintype "passive"))
      (node (ref "C33") (pin "1") (pinfunction "1_1") (pintype "passive"))
      (node (ref "C34") (pin "1") (pinfunction "1_1") (pintype "passive"))
      (node (ref "C35") (pin "1") (pinfunction "1_1") (pintype "passive"))
      (node (ref "C36") (pin "1") (pinfunction "1_1") (pintype "passive"))
      (node (ref "C38") (pin "-") (pinfunction "-_-") (pintype "passive"))
      (node (ref "C39") (pin "-") (pinfunction "-_-") (pintype "passive"))
      (node (ref "C4") (pin "1") (pinfunction "1_1") (pintype "passive"))
      (node (ref "C5") (pin "1") (pinfunction "1_1") (pintype "passive"))
      (node (ref "C6") (pin "1") (pinfunction "1_1") (pintype "passive"))
      (node (ref "C7") (pin "1") (pinfunction "1_1") (pintype "passive"))
      (node (ref "C8") (pin "1") (pinfunction "1_1") (pintype "passive"))
      (node (ref "C9") (pin "1") (pinfunction "1_1") (pintype "passive"))
      (node (ref "E1") (pin "3") (pinfunction "B_3") (pintype "input"))
      (node (ref "E1") (pin "4") (pinfunction "C_4") (pintype "input"))
      (node (ref "E1") (pin "5") (pinfunction "D_5") (pintype "input"))
      (node (ref "E17") (pin "1") (pinfunction "1G_1") (pintype "input"))
      (node (ref "E17") (pin "15") (pinfunction "2G_15") (pintype "input"))
      (node (ref "E18") (pin "1") (pinfunction "1G_1") (pintype "input"))
      (node (ref "E18") (pin "15") (pinfunction "2G_15") (pintype "input"))
      (node (ref "E19") (pin "1") (pinfunction "1G_1") (pintype "input"))
      (node (ref "E19") (pin "15") (pinfunction "2G_15") (pintype "input"))
      (node (ref "E2") (pin "3") (pinfunction "B_3") (pintype "input"))
      (node (ref "E2") (pin "4") (pinfunction "C_4") (pintype "input"))
      (node (ref "E2") (pin "5") (pinfunction "D_5") (pintype "input"))
      (node (ref "E3") (pin "3") (pinfunction "B_3") (pintype "input"))
      (node (ref "E3") (pin "4") (pinfunction "C_4") (pintype "input"))
      (node (ref "E3") (pin "5") (pinfunction "D_5") (pintype "input"))
      (node (ref "GND") (pin "1") (pinfunction "P_1") (pintype "passive"))
      (node (ref "J1") (pin "11") (pinfunction "11_11") (pintype "passive"))
      (node (ref "J1") (pin "13") (pinfunction "13_13") (pintype "passive"))
      (node (ref "J1") (pin "15") (pinfunction "15_15") (pintype "passive"))
      (node (ref "J1") (pin "17") (pinfunction "17_17") (pintype "passive"))
      (node (ref "J1") (pin "19") (pinfunction "19_19") (pintype "passive"))
      (node (ref "J1") (pin "21") (pinfunction "21_21") (pintype "passive"))
      (node (ref "J1") (pin "23") (pinfunction "23_23") (pintype "passive"))
      (node (ref "J1") (pin "25") (pinfunction "25_25") (pintype "passive"))
      (node (ref "J1") (pin "27") (pinfunction "27_27") (pintype "passive"))
      (node (ref "J1") (pin "29") (pinfunction "29_29") (pintype "passive"))
      (node (ref "J1") (pin "31") (pinfunction "31_31") (pintype "passive"))
      (node (ref "J1") (pin "33") (pinfunction "33_33") (pintype "passive"))
      (node (ref "J1") (pin "35") (pinfunction "35_35") (pintype "passive"))
      (node (ref "J1") (pin "37") (pinfunction "37_37") (pintype "passive"))
      (node (ref "J1") (pin "39") (pinfunction "39_39") (pintype "passive"))
      (node (ref "J2") (pin "11") (pinfunction "11_11") (pintype "passive"))
      (node (ref "J2") (pin "13") (pinfunction "13_13") (pintype "passive"))
      (node (ref "J2") (pin "15") (pinfunction "15_15") (pintype "passive"))
      (node (ref "J2") (pin "16") (pinfunction "16_16") (pintype "passive"))
      (node (ref "J2") (pin "17") (pinfunction "17_17") (pintype "passive"))
      (node (ref "J2") (pin "19") (pinfunction "19_19") (pintype "passive"))
      (node (ref "J2") (pin "21") (pinfunction "21_21") (pintype "passive"))
      (node (ref "J2") (pin "23") (pinfunction "23_23") (pintype "passive"))
      (node (ref "J2") (pin "25") (pinfunction "25_25") (pintype "passive"))
      (node (ref "J2") (pin "27") (pinfunction "27_27") (pintype "passive"))
      (node (ref "J2") (pin "29") (pinfunction "29_29") (pintype "passive"))
      (node (ref "J2") (pin "31") (pinfunction "31_31") (pintype "passive"))
      (node (ref "J2") (pin "33") (pinfunction "33_33") (pintype "passive"))
      (node (ref "J2") (pin "35") (pinfunction "35_35") (pintype "passive"))
      (node (ref "J2") (pin "37") (pinfunction "37_37") (pintype "passive"))
      (node (ref "J2") (pin "39") (pinfunction "39_39") (pintype "passive"))
      (node (ref "J3") (pin "8") (pinfunction "8_8") (pintype "passive"))
      (node (ref "J4") (pin "8") (pinfunction "8_8") (pintype "passive"))
      (node (ref "R1") (pin "1") (pinfunction "1_1") (pintype "passive"))
      (node (ref "R17") (pin "1") (pinfunction "1_1") (pintype "passive"))
      (node (ref "R18") (pin "1") (pinfunction "1_1") (pintype "passive"))
      (node (ref "R19") (pin "1") (pinfunction "1_1") (pintype "passive"))
      (node (ref "R2") (pin "1") (pinfunction "1_1") (pintype "passive"))
      (node (ref "R20") (pin "1") (pinfunction "1_1") (pintype "passive"))
      (node (ref "R21") (pin "1") (pinfunction "1_1") (pintype "passive"))
      (node (ref "R22") (pin "1") (pinfunction "1_1") (pintype "passive"))
      (node (ref "R23") (pin "1") (pinfunction "1_1") (pintype "passive"))
      (node (ref "R24") (pin "1") (pinfunction "1_1") (pintype "passive"))
      (node (ref "R27") (pin "2") (pinfunction "2_2") (pintype "passive"))
      (node (ref "R3") (pin "1") (pinfunction "1_1") (pintype "passive"))
      (node (ref "R30") (pin "2") (pinfunction "2_2") (pintype "passive"))
      (node (ref "R4") (pin "1") (pinfunction "1_1") (pintype "passive"))
    )
    (net (code "33") (name "KEYSTB") (class "Default")
      (node (ref "E24") (pin "1") (pinfunction "I_1") (pintype "input"))
      (node (ref "E8") (pin "5") (pinfunction "I1_5") (pintype "input"))
      (node (ref "J4") (pin "2") (pinfunction "2_2") (pintype "passive"))
    )
    (net (code "34") (name "LDSR") (class "Default")
      (node (ref "E33") (pin "13") (pinfunction "O_13") (pintype "output"))
      (node (ref "E5") (pin "9") (pinfunction "CLK_9") (pintype "input"))
      (node (ref "E6") (pin "9") (pinfunction "CLK_9") (pintype "input"))
      (node (ref "E7") (pin "9") (pinfunction "CLK_9") (pintype "input"))
    )
    (net (code "35") (name "MH0") (class "Default")
      (node (ref "E20") (pin "9") (pinfunction "Q_9") (pintype "output"))
      (node (ref "E22") (pin "11") (pinfunction "I0_11") (pintype "input"))
      (node (ref "E8") (pin "13") (pinfunction "I1_13") (pintype "input"))
    )
    (net (code "36") (name "MPXA") (class "Default")
      (node (ref "E17") (pin "14") (pinfunction "A_14") (pintype "input"))
      (node (ref "E18") (pin "14") (pinfunction "A_14") (pintype "input"))
      (node (ref "E19") (pin "14") (pinfunction "A_14") (pintype "input"))
      (node (ref "J4") (pin "14") (pinfunction "14_14") (pintype "passive"))
    )
    (net (code "37") (name "MPXB") (class "Default")
      (node (ref "E17") (pin "2") (pinfunction "B_2") (pintype "input"))
      (node (ref "E18") (pin "2") (pinfunction "B_2") (pintype "input"))
      (node (ref "E19") (pin "2") (pinfunction "B_2") (pintype "input"))
      (node (ref "J4") (pin "13") (pinfunction "13_13") (pintype "passive"))
    )
    (net (code "38") (name "NUM") (class "Default")
      (node (ref "E16") (pin "12") (pinfunction "D_12") (pintype "input"))
      (node (ref "E21") (pin "13") (pinfunction "I2_13") (pintype "input"))
      (node (ref "E8") (pin "4") (pinfunction "I0_4") (pintype "input"))
      (node (ref "J4") (pin "11") (pinfunction "11_11") (pintype "passive"))
    )
    (net (code "39") (name "NUMCLK") (class "Default")
      (node (ref "E1") (pin "8") (pinfunction "CK2_8") (pintype "input"))
      (node (ref "E1") (pin "9") (pinfunction "CK1_9") (pintype "input"))
      (node (ref "E2") (pin "8") (pinfunction "CK2_8") (pintype "input"))
      (node (ref "E2") (pin "9") (pinfunction "CK1_9") (pintype "input"))
      (node (ref "E3") (pin "8") (pinfunction "CK2_8") (pintype "input"))
      (node (ref "E3") (pin "9") (pinfunction "CK1_9") (pintype "input"))
      (node (ref "E8") (pin "6") (pinfunction "O_6") (pintype "output"))
    )
    (net (code "40") (name "Net-(E1A-QB)") (class "Default")
      (node (ref "E1") (pin "12") (pinfunction "QB_12") (pintype "output"))
      (node (ref "E5") (pin "13") (pinfunction "D4_13") (pintype "input"))
      (node (ref "E9") (pin "8") (pinfunction "A4_8") (pintype "input"))
    )
    (net (code "41") (name "Net-(E1A-QC)") (class "Default")
      (node (ref "E1") (pin "11") (pinfunction "QC_11") (pintype "output"))
      (node (ref "E5") (pin "4") (pinfunction "D1_4") (pintype "input"))
      (node (ref "E9") (pin "2") (pinfunction "A1_2") (pintype "input"))
    )
    (net (code "42") (name "Net-(E1A-QD)") (class "Default")
      (node (ref "E1") (pin "10") (pinfunction "QD_10") (pintype "output"))
      (node (ref "E5") (pin "5") (pinfunction "D2_5") (pintype "input"))
      (node (ref "E9") (pin "4") (pinfunction "A2_4") (pintype "input"))
    )
    (net (code "43") (name "Net-(E4B-C)") (class "Default")
      (node (ref "C37") (pin "1") (pinfunction "1_1") (pintype "passive"))
      (node (ref "C40") (pin "1") (pinfunction "1_1") (pintype "passive"))
      (node (ref "E4") (pin "6") (pinfunction "C_6") (pintype "input"))
    )
    (net (code "44") (name "Net-(E4B-Q)") (class "Default")
      (node (ref "E4") (pin "5") (pinfunction "Q_5") (pintype "output"))
      (node (ref "E8") (pin "10") (pinfunction "I1_10") (pintype "input"))
      (node (ref "E8") (pin "12") (pinfunction "I0_12") (pintype "input"))
    )
    (net (code "45") (name "Net-(E4B-R{slash}C)") (class "Default")
      (node (ref "C37") (pin "2") (pinfunction "2_2") (pintype "passive"))
      (node (ref "C40") (pin "2") (pinfunction "2_2") (pintype "passive"))
      (node (ref "E4") (pin "7") (pinfunction "R/C_7") (pintype "input"))
      (node (ref "R25") (pin "1") (pinfunction "1_1") (pintype "passive"))
    )
    (net (code "46") (name "Net-(E5A-Q1)") (class "Default")
      (node (ref "E5") (pin "2") (pinfunction "Q1_2") (pintype "output"))
      (node (ref "E9") (pin "17") (pinfunction "A4_17") (pintype "input"))
    )
    (net (code "47") (name "Net-(E5A-Q2)") (class "Default")
      (node (ref "E5") (pin "7") (pinfunction "Q2_7") (pintype "output"))
      (node (ref "E9") (pin "15") (pinfunction "A3_15") (pintype "input"))
    )
    (net (code "48") (name "Net-(E5A-Q3)") (class "Default")
      (node (ref "E5") (pin "10") (pinfunction "Q3_10") (pintype "output"))
      (node (ref "E9") (pin "13") (pinfunction "A2_13") (pintype "input"))
    )
    (net (code "49") (name "Net-(E5A-Q4)") (class "Default")
      (node (ref "E5") (pin "15") (pinfunction "Q4_15") (pintype "output"))
      (node (ref "E9") (pin "11") (pinfunction "A1_11") (pintype "input"))
    )
    (net (code "50") (name "Net-(E10A-A1)") (class "Default")
      (node (ref "E10") (pin "2") (pinfunction "A1_2") (pintype "input"))
      (node (ref "E2") (pin "11") (pinfunction "QC_11") (pintype "output"))
      (node (ref "E6") (pin "4") (pinfunction "D1_4") (pintype "input"))
    )
    (net (code "51") (name "Net-(E10A-A2)") (class "Default")
      (node (ref "E10") (pin "4") (pinfunction "A2_4") (pintype "input"))
      (node (ref "E2") (pin "10") (pinfunction "QD_10") (pintype "output"))
      (node (ref "E6") (pin "5") (pinfunction "D2_5") (pintype "input"))
    )
    (net (code "52") (name "Net-(E10A-A4)") (class "Default")
      (node (ref "E10") (pin "8") (pinfunction "A4_8") (pintype "input"))
      (node (ref "E2") (pin "12") (pinfunction "QB_12") (pintype "output"))
      (node (ref "E6") (pin "13") (pinfunction "D4_13") (pintype "input"))
    )
    (net (code "53") (name "Net-(E10B-A1)") (class "Default")
      (node (ref "E10") (pin "11") (pinfunction "A1_11") (pintype "input"))
      (node (ref "E6") (pin "15") (pinfunction "Q4_15") (pintype "output"))
    )
    (net (code "54") (name "Net-(E10B-A2)") (class "Default")
      (node (ref "E10") (pin "13") (pinfunction "A2_13") (pintype "input"))
      (node (ref "E6") (pin "10") (pinfunction "Q3_10") (pintype "output"))
    )
    (net (code "55") (name "Net-(E10B-A3)") (class "Default")
      (node (ref "E10") (pin "15") (pinfunction "A3_15") (pintype "input"))
      (node (ref "E6") (pin "7") (pinfunction "Q2_7") (pintype "output"))
    )
    (net (code "56") (name "Net-(E10B-A4)") (class "Default")
      (node (ref "E10") (pin "17") (pinfunction "A4_17") (pintype "input"))
      (node (ref "E6") (pin "2") (pinfunction "Q1_2") (pintype "output"))
    )
    (net (code "57") (name "Net-(E11A-A1)") (class "Default")
      (node (ref "E11") (pin "2") (pinfunction "A1_2") (pintype "input"))
      (node (ref "E3") (pin "11") (pinfunction "QC_11") (pintype "output"))
      (node (ref "E7") (pin "4") (pinfunction "D1_4") (pintype "input"))
    )
    (net (code "58") (name "Net-(E11A-A2)") (class "Default")
      (node (ref "E11") (pin "4") (pinfunction "A2_4") (pintype "input"))
      (node (ref "E3") (pin "10") (pinfunction "QD_10") (pintype "output"))
      (node (ref "E7") (pin "5") (pinfunction "D2_5") (pintype "input"))
    )
    (net (code "59") (name "Net-(E11A-A4)") (class "Default")
      (node (ref "E11") (pin "8") (pinfunction "A4_8") (pintype "input"))
      (node (ref "E3") (pin "12") (pinfunction "QB_12") (pintype "output"))
      (node (ref "E7") (pin "13") (pinfunction "D4_13") (pintype "input"))
    )
    (net (code "60") (name "Net-(E11B-A1)") (class "Default")
      (node (ref "E11") (pin "11") (pinfunction "A1_11") (pintype "input"))
      (node (ref "E7") (pin "15") (pinfunction "Q4_15") (pintype "output"))
    )
    (net (code "61") (name "Net-(E11B-A2)") (class "Default")
      (node (ref "E11") (pin "13") (pinfunction "A2_13") (pintype "input"))
      (node (ref "E7") (pin "10") (pinfunction "Q3_10") (pintype "output"))
    )
    (net (code "62") (name "Net-(E11B-A3)") (class "Default")
      (node (ref "E11") (pin "15") (pinfunction "A3_15") (pintype "input"))
      (node (ref "E7") (pin "7") (pinfunction "Q2_7") (pintype "output"))
    )
    (net (code "63") (name "Net-(E11B-A4)") (class "Default")
      (node (ref "E11") (pin "17") (pinfunction "A4_17") (pintype "input"))
      (node (ref "E7") (pin "2") (pinfunction "Q1_2") (pintype "output"))
    )
    (net (code "64") (name "Net-(E12A-Q1)") (class "Default")
      (node (ref "E12") (pin "2") (pinfunction "Q1_2") (pintype "output"))
      (node (ref "E17") (pin "4") (pinfunction "1C2_4") (pintype "input"))
    )
    (net (code "65") (name "Net-(E12A-Q2)") (class "Default")
      (node (ref "E12") (pin "5") (pinfunction "Q2_5") (pintype "output"))
      (node (ref "E17") (pin "6") (pinfunction "1C0_6") (pintype "input"))
    )
    (net (code "66") (name "Net-(E12A-Q3)") (class "Default")
      (node (ref "E12") (pin "7") (pinfunction "Q3_7") (pintype "output"))
      (node (ref "E17") (pin "13") (pinfunction "2C3_13") (pintype "input"))
    )
    (net (code "67") (name "Net-(E12A-Q4)") (class "Default")
      (node (ref "E12") (pin "10") (pinfunction "Q4_10") (pintype "output"))
      (node (ref "E17") (pin "11") (pinfunction "2C1_11") (pintype "input"))
    )
    (net (code "68") (name "Net-(E12A-Q5)") (class "Default")
      (node (ref "E12") (pin "12") (pinfunction "Q5_12") (pintype "output"))
      (node (ref "E17") (pin "12") (pinfunction "2C2_12") (pintype "input"))
    )
    (net (code "69") (name "Net-(E12A-Q6)") (class "Default")
      (node (ref "E12") (pin "15") (pinfunction "Q6_15") (pintype "output"))
      (node (ref "E17") (pin "10") (pinfunction "2C0_10") (pintype "input"))
    )
    (net (code "70") (name "Net-(E13A-Q1)") (class "Default")
      (node (ref "E13") (pin "2") (pinfunction "Q1_2") (pintype "output"))
      (node (ref "E19") (pin "12") (pinfunction "2C2_12") (pintype "input"))
    )
    (net (code "71") (name "Net-(E13A-Q2)") (class "Default")
      (node (ref "E13") (pin "5") (pinfunction "Q2_5") (pintype "output"))
      (node (ref "E19") (pin "10") (pinfunction "2C0_10") (pintype "input"))
    )
    (net (code "72") (name "Net-(E13A-Q3)") (class "Default")
      (node (ref "E13") (pin "7") (pinfunction "Q3_7") (pintype "output"))
      (node (ref "E18") (pin "3") (pinfunction "1C3_3") (pintype "input"))
    )
    (net (code "73") (name "Net-(E13A-Q4)") (class "Default")
      (node (ref "E13") (pin "10") (pinfunction "Q4_10") (pintype "output"))
      (node (ref "E18") (pin "5") (pinfunction "1C1_5") (pintype "input"))
    )
    (net (code "74") (name "Net-(E13A-Q5)") (class "Default")
      (node (ref "E13") (pin "12") (pinfunction "Q5_12") (pintype "output"))
      (node (ref "E18") (pin "4") (pinfunction "1C2_4") (pintype "input"))
    )
    (net (code "75") (name "Net-(E13A-Q6)") (class "Default")
      (node (ref "E13") (pin "15") (pinfunction "Q6_15") (pintype "output"))
      (node (ref "E18") (pin "6") (pinfunction "1C0_6") (pintype "input"))
    )
    (net (code "76") (name "Net-(E14A-Q1)") (class "Default")
      (node (ref "E14") (pin "2") (pinfunction "Q1_2") (pintype "output"))
      (node (ref "E18") (pin "13") (pinfunction "2C3_13") (pintype "input"))
    )
    (net (code "77") (name "Net-(E14A-Q2)") (class "Default")
      (node (ref "E14") (pin "5") (pinfunction "Q2_5") (pintype "output"))
      (node (ref "E18") (pin "11") (pinfunction "2C1_11") (pintype "input"))
    )
    (net (code "78") (name "Net-(E14A-Q3)") (class "Default")
      (node (ref "E14") (pin "7") (pinfunction "Q3_7") (pintype "output"))
      (node (ref "E18") (pin "12") (pinfunction "2C2_12") (pintype "input"))
    )
    (net (code "79") (name "Net-(E14A-Q4)") (class "Default")
      (node (ref "E14") (pin "10") (pinfunction "Q4_10") (pintype "output"))
      (node (ref "E18") (pin "10") (pinfunction "2C0_10") (pintype "input"))
    )
    (net (code "80") (name "Net-(E14A-Q5)") (class "Default")
      (node (ref "E14") (pin "12") (pinfunction "Q5_12") (pintype "output"))
      (node (ref "E17") (pin "3") (pinfunction "1C3_3") (pintype "input"))
    )
    (net (code "81") (name "Net-(E14A-Q6)") (class "Default")
      (node (ref "E14") (pin "15") (pinfunction "Q6_15") (pintype "output"))
      (node (ref "E17") (pin "5") (pinfunction "1C1_5") (pintype "input"))
    )
    (net (code "82") (name "Net-(E15A-Q1)") (class "Default")
      (node (ref "E15") (pin "2") (pinfunction "Q1_2") (pintype "output"))
      (node (ref "E19") (pin "3") (pinfunction "1C3_3") (pintype "input"))
    )
    (net (code "83") (name "Net-(E15A-Q2)") (class "Default")
      (node (ref "E15") (pin "5") (pinfunction "Q2_5") (pintype "output"))
      (node (ref "E19") (pin "5") (pinfunction "1C1_5") (pintype "input"))
    )
    (net (code "84") (name "Net-(E15A-Q3)") (class "Default")
      (node (ref "E15") (pin "7") (pinfunction "Q3_7") (pintype "output"))
      (node (ref "E19") (pin "4") (pinfunction "1C2_4") (pintype "input"))
    )
    (net (code "85") (name "Net-(E15A-Q4)") (class "Default")
      (node (ref "E15") (pin "10") (pinfunction "Q4_10") (pintype "output"))
      (node (ref "E19") (pin "6") (pinfunction "1C0_6") (pintype "input"))
    )
    (net (code "86") (name "Net-(E15A-Q5)") (class "Default")
      (node (ref "E15") (pin "12") (pinfunction "Q5_12") (pintype "output"))
      (node (ref "E19") (pin "13") (pinfunction "2C3_13") (pintype "input"))
    )
    (net (code "87") (name "Net-(E15A-Q6)") (class "Default")
      (node (ref "E15") (pin "15") (pinfunction "Q6_15") (pintype "output"))
      (node (ref "E19") (pin "11") (pinfunction "2C1_11") (pintype "input"))
    )
    (net (code "88") (name "Net-(E16A-CLK)") (class "Default")
      (node (ref "E16") (pin "3") (pinfunction "CLK_3") (pintype "input"))
      (node (ref "E21") (pin "12") (pinfunction "O_12") (pintype "output"))
    )
    (net (code "89") (name "Net-(E20A-PRE)") (class "Default")
      (node (ref "E20") (pin "4") (pinfunction "PRE_4") (pintype "input"))
      (node (ref "E26") (pin "8") (pinfunction "~{Q4}_8") (pintype "output"))
    )
    (net (code "90") (name "Net-(E20B-CLK)") (class "Default")
      (node (ref "E20") (pin "11") (pinfunction "CLK_11") (pintype "input"))
      (node (ref "E22") (pin "1") (pinfunction "O_1") (pintype "output"))
      (node (ref "E4") (pin "9") (pinfunction "A_9") (pintype "input"))
    )
    (net (code "91") (name "Net-(E21A-I0)") (class "Default")
      (node (ref "E21") (pin "1") (pinfunction "I0_1") (pintype "input"))
      (node (ref "E24") (pin "4") (pinfunction "O_4") (pintype "output"))
    )
    (net (code "92") (name "Net-(E21B-I0)") (class "Default")
      (node (ref "E21") (pin "3") (pinfunction "I0_3") (pintype "input"))
      (node (ref "E21") (pin "4") (pinfunction "I1_4") (pintype "input"))
      (node (ref "E22") (pin "4") (pinfunction "O_4") (pintype "output"))
    )
    (net (code "93") (name "Net-(E21C-O)") (class "Default")
      (node (ref "E21") (pin "8") (pinfunction "O_8") (pintype "output"))
      (node (ref "E23") (pin "9") (pinfunction "I_9") (pintype "input"))
    )
    (net (code "94") (name "Net-(E22A-I0)") (class "Default")
      (node (ref "E22") (pin "2") (pinfunction "I0_2") (pintype "input"))
      (node (ref "E32") (pin "6") (pinfunction "O_6") (pintype "output"))
    )
    (net (code "95") (name "Net-(E22A-I1)") (class "Default")
      (node (ref "E22") (pin "3") (pinfunction "I1_3") (pintype "input"))
      (node (ref "E33") (pin "1") (pinfunction "O_1") (pintype "output"))
    )
    (net (code "96") (name "Net-(E22B-I0)") (class "Default")
      (node (ref "E22") (pin "5") (pinfunction "I0_5") (pintype "input"))
      (node (ref "E8") (pin "3") (pinfunction "O_3") (pintype "output"))
    )
    (net (code "97") (name "Net-(E22C-I0)") (class "Default")
      (node (ref "E22") (pin "8") (pinfunction "I0_8") (pintype "input"))
      (node (ref "E25") (pin "12") (pinfunction "O_12") (pintype "output"))
    )
    (net (code "98") (name "Net-(E22C-I1)") (class "Default")
      (node (ref "E22") (pin "9") (pinfunction "I1_9") (pintype "input"))
      (node (ref "E25") (pin "8") (pinfunction "O_8") (pintype "output"))
    )
    (net (code "99") (name "Net-(E22C-O)") (class "Default")
      (node (ref "E22") (pin "10") (pinfunction "O_10") (pintype "output"))
      (node (ref "E29") (pin "4") (pinfunction "G2A_4") (pintype "input"))
      (node (ref "E29") (pin "5") (pinfunction "G2B_5") (pintype "input"))
      (node (ref "E31") (pin "15") (pinfunction "2G_15") (pintype "input"))
    )
    (net (code "100") (name "Net-(E22D-O)") (class "Default")
      (node (ref "E22") (pin "13") (pinfunction "O_13") (pintype "output"))
      (node (ref "E30") (pin "4") (pinfunction "I0_4") (pintype "input"))
    )
    (net (code "101") (name "Net-(E23A-I)") (class "Default")
      (node (ref "E23") (pin "1") (pinfunction "I_1") (pintype "input"))
      (node (ref "E33") (pin "4") (pinfunction "O_4") (pintype "output"))
    )
    (net (code "102") (name "Net-(E23E-I)") (class "Default")
      (node (ref "E23") (pin "11") (pinfunction "I_11") (pintype "input"))
      (node (ref "E24") (pin "10") (pinfunction "O_10") (pintype "output"))
    )
    (net (code "103") (name "Net-(E24D-O)") (class "Default")
      (node (ref "E24") (pin "8") (pinfunction "O_8") (pintype "output"))
      (node (ref "E32") (pin "5") (pinfunction "I1_5") (pintype "input"))
    )
    (net (code "104") (name "Net-(E24F-O)") (class "Default")
      (node (ref "E24") (pin "12") (pinfunction "O_12") (pintype "output"))
      (node (ref "E25") (pin "10") (pinfunction "I1_10") (pintype "input"))
      (node (ref "E28") (pin "1") (pinfunction "1G_1") (pintype "input"))
      (node (ref "E28") (pin "15") (pinfunction "2G_15") (pintype "input"))
      (node (ref "E33") (pin "6") (pinfunction "I1_6") (pintype "input"))
    )
    (net (code "105") (name "Net-(E25A-I0)") (class "Default")
      (node (ref "E25") (pin "1") (pinfunction "I0_1") (pintype "input"))
      (node (ref "E26") (pin "16") (pinfunction "Q1_16") (pintype "output"))
      (node (ref "E29") (pin "3") (pinfunction "C_3") (pintype "input"))
    )
    (net (code "106") (name "Net-(E25A-I2)") (class "Default")
      (node (ref "E25") (pin "13") (pinfunction "I2_13") (pintype "input"))
      (node (ref "E26") (pin "15") (pinfunction "Q2_15") (pintype "output"))
      (node (ref "E27") (pin "3") (pinfunction "I_3") (pintype "input"))
      (node (ref "E29") (pin "2") (pinfunction "B_2") (pintype "input"))
      (node (ref "E30") (pin "1") (pinfunction "I0_1") (pintype "input"))
    )
    (net (code "107") (name "Net-(E25C-I0)") (class "Default")
      (node (ref "E25") (pin "9") (pinfunction "I0_9") (pintype "input"))
      (node (ref "E26") (pin "9") (pinfunction "Q4_9") (pintype "output"))
    )
    (net (code "108") (name "Net-(E26A-Q3)") (class "Default")
      (node (ref "E26") (pin "10") (pinfunction "Q3_10") (pintype "output"))
      (node (ref "E29") (pin "1") (pinfunction "A_1") (pintype "input"))
    )
    (net (code "109") (name "Net-(E27A-O)") (class "Default")
      (node (ref "E27") (pin "2") (pinfunction "O_2") (pintype "output"))
      (node (ref "E30") (pin "12") (pinfunction "I0_12") (pintype "input"))
    )
    (net (code "110") (name "Net-(E27B-O)") (class "Default")
      (node (ref "E27") (pin "4") (pinfunction "O_4") (pintype "output"))
      (node (ref "E31") (pin "12") (pinfunction "2A1_12") (pintype "input"))
    )
    (net (code "111") (name "Net-(E27C-O)") (class "Default")
      (node (ref "E27") (pin "6") (pinfunction "O_6") (pintype "output"))
      (node (ref "E30") (pin "13") (pinfunction "I1_13") (pintype "input"))
    )
    (net (code "112") (name "Net-(E28A-1A1)") (class "Default")
      (node (ref "E28") (pin "2") (pinfunction "1A1_2") (pintype "input"))
      (node (ref "E29") (pin "9") (pinfunction "Y6_9") (pintype "output"))
      (node (ref "E32") (pin "2") (pinfunction "I1_2") (pintype "input"))
    )
    (net (code "113") (name "Net-(E28A-1A2)") (class "Default")
      (node (ref "E28") (pin "4") (pinfunction "1A2_4") (pintype "input"))
      (node (ref "E29") (pin "7") (pinfunction "Y7_7") (pintype "output"))
      (node (ref "E30") (pin "10") (pinfunction "I1_10") (pintype "input"))
      (node (ref "E32") (pin "1") (pinfunction "I0_1") (pintype "input"))
    )
    (net (code "114") (name "Net-(E28A-1A3)") (class "Default")
      (node (ref "E28") (pin "6") (pinfunction "1A3_6") (pintype "input"))
      (node (ref "E30") (pin "9") (pinfunction "I0_9") (pintype "input"))
      (node (ref "E31") (pin "6") (pinfunction "1A3_6") (pintype "input"))
      (node (ref "E32") (pin "8") (pinfunction "O_8") (pintype "output"))
      (node (ref "E33") (pin "5") (pinfunction "I0_5") (pintype "input"))
    )
    (net (code "115") (name "Net-(E28A-2A2)") (class "Default")
      (node (ref "E28") (pin "14") (pinfunction "2A2_14") (pintype "input"))
      (node (ref "E30") (pin "11") (pinfunction "O_11") (pintype "output"))
    )
    (net (code "116") (name "Net-(E29A-Y0)") (class "Default")
      (node (ref "E29") (pin "15") (pinfunction "Y0_15") (pintype "output"))
      (node (ref "E33") (pin "8") (pinfunction "I0_8") (pintype "input"))
    )
    (net (code "117") (name "Net-(E29A-Y1)") (class "Default")
      (node (ref "E29") (pin "14") (pinfunction "Y1_14") (pintype "output"))
      (node (ref "E33") (pin "12") (pinfunction "I1_12") (pintype "input"))
    )
    (net (code "118") (name "Net-(E29A-Y2)") (class "Default")
      (node (ref "E29") (pin "13") (pinfunction "Y2_13") (pintype "output"))
      (node (ref "E30") (pin "2") (pinfunction "I1_2") (pintype "input"))
      (node (ref "E32") (pin "10") (pinfunction "I1_10") (pintype "input"))
    )
    (net (code "119") (name "Net-(E29A-Y3)") (class "Default")
      (node (ref "E29") (pin "12") (pinfunction "Y3_12") (pintype "output"))
      (node (ref "E32") (pin "9") (pinfunction "I0_9") (pintype "input"))
    )
    (net (code "120") (name "Net-(E29A-Y4)") (class "Default")
      (node (ref "E29") (pin "11") (pinfunction "Y4_11") (pintype "output"))
      (node (ref "E31") (pin "10") (pinfunction "1A4_10") (pintype "input"))
    )
    (net (code "121") (name "Net-(E29A-Y5)") (class "Default")
      (node (ref "E29") (pin "10") (pinfunction "Y5_10") (pintype "output"))
      (node (ref "E31") (pin "2") (pinfunction "1A1_2") (pintype "input"))
    )
    (net (code "122") (name "Net-(E30A-O)") (class "Default")
      (node (ref "E30") (pin "3") (pinfunction "O_3") (pintype "output"))
      (node (ref "E31") (pin "14") (pinfunction "2A2_14") (pintype "input"))
    )
    (net (code "123") (name "Net-(E30B-O)") (class "Default")
      (node (ref "E30") (pin "6") (pinfunction "O_6") (pintype "output"))
      (node (ref "E34") (pin "1") (pinfunction "1G_1") (pintype "input"))
      (node (ref "E34") (pin "15") (pinfunction "2G_15") (pintype "input"))
      (node (ref "E35") (pin "4") (pinfunction "G2A_4") (pintype "input"))
      (node (ref "E35") (pin "5") (pinfunction "G2B_5") (pintype "input"))
    )
    (net (code "124") (name "Net-(E31A-1A2)") (class "Default")
      (node (ref "E31") (pin "4") (pinfunction "1A2_4") (pintype "input"))
      (node (ref "E32") (pin "3") (pinfunction "O_3") (pintype "output"))
    )
    (net (code "125") (name "Net-(E32D-I0)") (class "Default")
      (node (ref "E32") (pin "12") (pinfunction "I0_12") (pintype "input"))
      (node (ref "E35") (pin "11") (pinfunction "Y4_11") (pintype "output"))
    )
    (net (code "126") (name "Net-(E33C-O)") (class "Default")
      (node (ref "E33") (pin "10") (pinfunction "O_10") (pintype "output"))
      (node (ref "E36") (pin "9") (pinfunction "CLK_9") (pintype "input"))
    )
    (net (code "127") (name "Net-(E34A-1A3)") (class "Default")
      (node (ref "E34") (pin "6") (pinfunction "1A3_6") (pintype "input"))
      (node (ref "E35") (pin "9") (pinfunction "Y6_9") (pintype "output"))
    )
    (net (code "128") (name "Net-(E34A-2A1)") (class "Default")
      (node (ref "E34") (pin "12") (pinfunction "2A1_12") (pintype "input"))
      (node (ref "E35") (pin "10") (pinfunction "Y5_10") (pintype "output"))
    )
    (net (code "129") (name "POWCK") (class "Default")
      (node (ref "E24") (pin "11") (pinfunction "I_11") (pintype "input"))
      (node (ref "J2") (pin "28") (pinfunction "28_28") (pintype "passive"))
      (node (ref "R33") (pin "2") (pinfunction "2_2") (pintype "passive"))
    )
    (net (code "130") (name "THIS") (class "Default")
      (node (ref "E20") (pin "5") (pinfunction "Q_5") (pintype "output"))
      (node (ref "E28") (pin "12") (pinfunction "2A1_12") (pintype "input"))
    )
    (net (code "131") (name "VCC") (class "Default")
      (node (ref "C1") (pin "2") (pinfunction "2_2") (pintype "passive"))
      (node (ref "C10") (pin "2") (pinfunction "2_2") (pintype "passive"))
      (node (ref "C11") (pin "2") (pinfunction "2_2") (pintype "passive"))
      (node (ref "C12") (pin "2") (pinfunction "2_2") (pintype "passive"))
      (node (ref "C13") (pin "2") (pinfunction "2_2") (pintype "passive"))
      (node (ref "C14") (pin "2") (pinfunction "2_2") (pintype "passive"))
      (node (ref "C15") (pin "2") (pinfunction "2_2") (pintype "passive"))
      (node (ref "C16") (pin "2") (pinfunction "2_2") (pintype "passive"))
      (node (ref "C17") (pin "2") (pinfunction "2_2") (pintype "passive"))
      (node (ref "C18") (pin "2") (pinfunction "2_2") (pintype "passive"))
      (node (ref "C19") (pin "2") (pinfunction "2_2") (pintype "passive"))
      (node (ref "C2") (pin "2") (pinfunction "2_2") (pintype "passive"))
      (node (ref "C20") (pin "2") (pinfunction "2_2") (pintype "passive"))
      (node (ref "C21") (pin "2") (pinfunction "2_2") (pintype "passive"))
      (node (ref "C22") (pin "2") (pinfunction "2_2") (pintype "passive"))
      (node (ref "C23") (pin "2") (pinfunction "2_2") (pintype "passive"))
      (node (ref "C24") (pin "2") (pinfunction "2_2") (pintype "passive"))
      (node (ref "C25") (pin "2") (pinfunction "2_2") (pintype "passive"))
      (node (ref "C26") (pin "2") (pinfunction "2_2") (pintype "passive"))
      (node (ref "C27") (pin "2") (pinfunction "2_2") (pintype "passive"))
      (node (ref "C28") (pin "2") (pinfunction "2_2") (pintype "passive"))
      (node (ref "C29") (pin "2") (pinfunction "2_2") (pintype "passive"))
      (node (ref "C3") (pin "2") (pinfunction "2_2") (pintype "passive"))
      (node (ref "C30") (pin "2") (pinfunction "2_2") (pintype "passive"))
      (node (ref "C31") (pin "2") (pinfunction "2_2") (pintype "passive"))
      (node (ref "C32") (pin "2") (pinfunction "2_2") (pintype "passive"))
      (node (ref "C33") (pin "2") (pinfunction "2_2") (pintype "passive"))
      (node (ref "C34") (pin "2") (pinfunction "2_2") (pintype "passive"))
      (node (ref "C35") (pin "2") (pinfunction "2_2") (pintype "passive"))
      (node (ref "C36") (pin "2") (pinfunction "2_2") (pintype "passive"))
      (node (ref "C38") (pin "+") (pinfunction "+_+") (pintype "passive"))
      (node (ref "C39") (pin "+") (pinfunction "+_+") (pintype "passive"))
      (node (ref "C4") (pin "2") (pinfunction "2_2") (pintype "passive"))
      (node (ref "C5") (pin "2") (pinfunction "2_2") (pintype "passive"))
      (node (ref "C6") (pin "2") (pinfunction "2_2") (pintype "passive"))
      (node (ref "C7") (pin "2") (pinfunction "2_2") (pintype "passive"))
      (node (ref "C8") (pin "2") (pinfunction "2_2") (pintype "passive"))
      (node (ref "C9") (pin "2") (pinfunction "2_2") (pintype "passive"))
      (node (ref "E16") (pin "10") (pinfunction "PRE_10") (pintype "input"))
      (node (ref "E16") (pin "4") (pinfunction "PRE_4") (pintype "input"))
      (node (ref "E20") (pin "10") (pinfunction "PRE_10") (pintype "input"))
      (node (ref "E29") (pin "6") (pinfunction "G1_6") (pintype "input"))
      (node (ref "E34") (pin "10") (pinfunction "1A4_10") (pintype "input"))
      (node (ref "E35") (pin "6") (pinfunction "G1_6") (pintype "input"))
      (node (ref "E36") (pin "1") (pinfunction "CLR_1") (pintype "input"))
      (node (ref "E36") (pin "11") (pinfunction "D4_11") (pintype "input"))
      (node (ref "E36") (pin "13") (pinfunction "D5_13") (pintype "input"))
      (node (ref "E36") (pin "6") (pinfunction "D3_6") (pintype "input"))
      (node (ref "E4") (pin "10") (pinfunction "B_10") (pintype "input"))
      (node (ref "E4") (pin "11") (pinfunction "CLR_11") (pintype "input"))
      (node (ref "J1") (pin "1") (pinfunction "1_1") (pintype "passive"))
      (node (ref "J1") (pin "2") (pinfunction "2_2") (pintype "passive"))
      (node (ref "J1") (pin "3") (pinfunction "3_3") (pintype "passive"))
      (node (ref "J1") (pin "4") (pinfunction "4_4") (pintype "passive"))
      (node (ref "J1") (pin "5") (pinfunction "5_5") (pintype "passive"))
      (node (ref "J1") (pin "7") (pinfunction "7_7") (pintype "passive"))
      (node (ref "J1") (pin "9") (pinfunction "9_9") (pintype "passive"))
      (node (ref "J2") (pin "1") (pinfunction "1_1") (pintype "passive"))
      (node (ref "J2") (pin "3") (pinfunction "3_3") (pintype "passive"))
      (node (ref "J2") (pin "5") (pinfunction "5_5") (pintype "passive"))
      (node (ref "J2") (pin "7") (pinfunction "7_7") (pintype "passive"))
      (node (ref "J2") (pin "9") (pinfunction "9_9") (pintype "passive"))
      (node (ref "J3") (pin "16") (pinfunction "16_16") (pintype "passive"))
      (node (ref "J4") (pin "16") (pinfunction "16_16") (pintype "passive"))
      (node (ref "R10") (pin "2") (pinfunction "2_2") (pintype "passive"))
      (node (ref "R11") (pin "2") (pinfunction "2_2") (pintype "passive"))
      (node (ref "R12") (pin "2") (pinfunction "2_2") (pintype "passive"))
      (node (ref "R13") (pin "2") (pinfunction "2_2") (pintype "passive"))
      (node (ref "R14") (pin "2") (pinfunction "2_2") (pintype "passive"))
      (node (ref "R15") (pin "2") (pinfunction "2_2") (pintype "passive"))
      (node (ref "R16") (pin "2") (pinfunction "2_2") (pintype "passive"))
      (node (ref "R25") (pin "2") (pinfunction "2_2") (pintype "passive"))
      (node (ref "R26") (pin "1") (pinfunction "1_1") (pintype "passive"))
      (node (ref "R28") (pin "2") (pinfunction "2_2") (pintype "passive"))
      (node (ref "R29") (pin "1") (pinfunction "1_1") (pintype "passive"))
      (node (ref "R31") (pin "1") (pinfunction "1_1") (pintype "passive"))
      (node (ref "R32") (pin "1") (pinfunction "1_1") (pintype "passive"))
      (node (ref "R33") (pin "1") (pinfunction "1_1") (pintype "passive"))
      (node (ref "R34") (pin "1") (pinfunction "1_1") (pintype "passive"))
      (node (ref "R35") (pin "1") (pinfunction "1_1") (pintype "passive"))
      (node (ref "R36") (pin "1") (pinfunction "1_1") (pintype "passive"))
      (node (ref "R5") (pin "2") (pinfunction "2_2") (pintype "passive"))
      (node (ref "R6") (pin "2") (pinfunction "2_2") (pintype "passive"))
      (node (ref "R7") (pin "2") (pinfunction "2_2") (pintype "passive"))
      (node (ref "R8") (pin "2") (pinfunction "2_2") (pintype "passive"))
      (node (ref "R9") (pin "2") (pinfunction "2_2") (pintype "passive"))
      (node (ref "VCC") (pin "1") (pinfunction "P_1") (pintype "passive"))
    )
    (net (code "132") (name "unconnected-(D1-PadA)") (class "Default")
      (node (ref "D1") (pin "A") (pinfunction "A_A") (pintype "passive"))
    )
    (net (code "133") (name "unconnected-(D1-PadC)") (class "Default")
      (node (ref "D1") (pin "C") (pinfunction "C_C") (pintype "passive"))
    )
    (net (code "134") (name "unconnected-(D2-PadA)") (class "Default")
      (node (ref "D2") (pin "A") (pinfunction "A_A") (pintype "passive"))
    )
    (net (code "135") (name "unconnected-(D2-PadC)") (class "Default")
      (node (ref "D2") (pin "C") (pinfunction "C_C") (pintype "passive"))
    )
    (net (code "136") (name "unconnected-(E4B-~{Q}-Pad12)") (class "Default")
      (node (ref "E4") (pin "12") (pinfunction "~{Q}_12") (pintype "output"))
    )
    (net (code "137") (name "unconnected-(E5A-~{Q1}-Pad3)") (class "Default")
      (node (ref "E5") (pin "3") (pinfunction "~{Q1}_3") (pintype "output"))
    )
    (net (code "138") (name "unconnected-(E5A-~{Q2}-Pad6)") (class "Default")
      (node (ref "E5") (pin "6") (pinfunction "~{Q2}_6") (pintype "output"))
    )
    (net (code "139") (name "unconnected-(E5A-~{Q3}-Pad11)") (class "Default")
      (node (ref "E5") (pin "11") (pinfunction "~{Q3}_11") (pintype "output"))
    )
    (net (code "140") (name "unconnected-(E5A-~{Q4}-Pad14)") (class "Default")
      (node (ref "E5") (pin "14") (pinfunction "~{Q4}_14") (pintype "output"))
    )
    (net (code "141") (name "unconnected-(E6A-~{Q1}-Pad3)") (class "Default")
      (node (ref "E6") (pin "3") (pinfunction "~{Q1}_3") (pintype "output"))
    )
    (net (code "142") (name "unconnected-(E6A-~{Q2}-Pad6)") (class "Default")
      (node (ref "E6") (pin "6") (pinfunction "~{Q2}_6") (pintype "output"))
    )
    (net (code "143") (name "unconnected-(E6A-~{Q3}-Pad11)") (class "Default")
      (node (ref "E6") (pin "11") (pinfunction "~{Q3}_11") (pintype "output"))
    )
    (net (code "144") (name "unconnected-(E6A-~{Q4}-Pad14)") (class "Default")
      (node (ref "E6") (pin "14") (pinfunction "~{Q4}_14") (pintype "output"))
    )
    (net (code "145") (name "unconnected-(E7A-~{Q1}-Pad3)") (class "Default")
      (node (ref "E7") (pin "3") (pinfunction "~{Q1}_3") (pintype "output"))
    )
    (net (code "146") (name "unconnected-(E7A-~{Q2}-Pad6)") (class "Default")
      (node (ref "E7") (pin "6") (pinfunction "~{Q2}_6") (pintype "output"))
    )
    (net (code "147") (name "unconnected-(E7A-~{Q3}-Pad11)") (class "Default")
      (node (ref "E7") (pin "11") (pinfunction "~{Q3}_11") (pintype "output"))
    )
    (net (code "148") (name "unconnected-(E7A-~{Q4}-Pad14)") (class "Default")
      (node (ref "E7") (pin "14") (pinfunction "~{Q4}_14") (pintype "output"))
    )
    (net (code "149") (name "unconnected-(E16A-Q-Pad5)") (class "Default")
      (node (ref "E16") (pin "5") (pinfunction "Q_5") (pintype "output"))
    )
    (net (code "150") (name "unconnected-(E20A-~{Q}-Pad6)") (class "Default")
      (node (ref "E20") (pin "6") (pinfunction "~{Q}_6") (pintype "output"))
    )
    (net (code "151") (name "unconnected-(E26A-~{Q1}-Pad1)") (class "Default")
      (node (ref "E26") (pin "1") (pinfunction "~{Q1}_1") (pintype "output"))
    )
    (net (code "152") (name "unconnected-(E26A-~{Q2}-Pad14)") (class "Default")
      (node (ref "E26") (pin "14") (pinfunction "~{Q2}_14") (pintype "output"))
    )
    (net (code "153") (name "unconnected-(E26A-~{Q3}-Pad11)") (class "Default")
      (node (ref "E26") (pin "11") (pinfunction "~{Q3}_11") (pintype "output"))
    )
    (net (code "154") (name "unconnected-(E34A-1Y4-Pad9)") (class "Default")
      (node (ref "E34") (pin "9") (pinfunction "1Y4_9") (pintype "tri_state"))
    )
    (net (code "155") (name "unconnected-(E35A-Y0-Pad15)") (class "Default")
      (node (ref "E35") (pin "15") (pinfunction "Y0_15") (pintype "output"))
    )
    (net (code "156") (name "unconnected-(E35A-Y1-Pad14)") (class "Default")
      (node (ref "E35") (pin "14") (pinfunction "Y1_14") (pintype "output"))
    )
    (net (code "157") (name "unconnected-(E35A-Y2-Pad13)") (class "Default")
      (node (ref "E35") (pin "13") (pinfunction "Y2_13") (pintype "output"))
    )
    (net (code "158") (name "unconnected-(E35A-Y3-Pad12)") (class "Default")
      (node (ref "E35") (pin "12") (pinfunction "Y3_12") (pintype "output"))
    )
    (net (code "159") (name "unconnected-(E35A-Y7-Pad7)") (class "Default")
      (node (ref "E35") (pin "7") (pinfunction "Y7_7") (pintype "output"))
    )
    (net (code "160") (name "unconnected-(E36A-Q3-Pad7)") (class "Default")
      (node (ref "E36") (pin "7") (pinfunction "Q3_7") (pintype "output"))
    )
    (net (code "161") (name "unconnected-(E36A-Q4-Pad10)") (class "Default")
      (node (ref "E36") (pin "10") (pinfunction "Q4_10") (pintype "output"))
    )
    (net (code "162") (name "unconnected-(E36A-Q5-Pad12)") (class "Default")
      (node (ref "E36") (pin "12") (pinfunction "Q5_12") (pintype "output"))
    )
    (net (code "163") (name "~{ADRLTH}") (class "Default")
      (node (ref "E12") (pin "9") (pinfunction "CLK_9") (pintype "input"))
      (node (ref "E14") (pin "9") (pinfunction "CLK_9") (pintype "input"))
      (node (ref "E8") (pin "11") (pinfunction "O_11") (pintype "output"))
    )
    (net (code "164") (name "~{BFSW}") (class "Default")
      (node (ref "E28") (pin "9") (pinfunction "1Y4_9") (pintype "tri_state"))
      (node (ref "J2") (pin "24") (pinfunction "24_24") (pintype "passive"))
    )
    (net (code "165") (name "~{BKDTACNTL}") (class "Default")
      (node (ref "E28") (pin "3") (pinfunction "1Y1_3") (pintype "tri_state"))
      (node (ref "J2") (pin "12") (pinfunction "12_12") (pintype "passive"))
    )
    (net (code "166") (name "~{BOOTF}") (class "Default")
      (node (ref "E16") (pin "2") (pinfunction "D_2") (pintype "input"))
      (node (ref "E16") (pin "6") (pinfunction "~{Q}_6") (pintype "output"))
      (node (ref "E28") (pin "10") (pinfunction "1A4_10") (pintype "input"))
    )
    (net (code "167") (name "~{BUSEN}") (class "Default")
      (node (ref "E34") (pin "13") (pinfunction "2Y2_13") (pintype "tri_state"))
      (node (ref "J1") (pin "24") (pinfunction "24_24") (pintype "passive"))
    )
    (net (code "168") (name "~{DEP}") (class "Default")
      (node (ref "E28") (pin "5") (pinfunction "1Y2_5") (pintype "tri_state"))
      (node (ref "J2") (pin "20") (pinfunction "20_20") (pintype "passive"))
    )
    (net (code "169") (name "~{DSPLTH}") (class "Default")
      (node (ref "E13") (pin "9") (pinfunction "CLK_9") (pintype "input"))
      (node (ref "E15") (pin "9") (pinfunction "CLK_9") (pintype "input"))
      (node (ref "E8") (pin "8") (pinfunction "O_8") (pintype "output"))
    )
    (net (code "170") (name "~{EMA0}") (class "Default")
      (node (ref "E27") (pin "11") (pinfunction "I_11") (pintype "input"))
      (node (ref "J1") (pin "30") (pinfunction "30_30") (pintype "passive"))
      (node (ref "R34") (pin "2") (pinfunction "2_2") (pintype "passive"))
    )
    (net (code "171") (name "~{EMA1}") (class "Default")
      (node (ref "E27") (pin "9") (pinfunction "I_9") (pintype "input"))
      (node (ref "J1") (pin "28") (pinfunction "28_28") (pintype "passive"))
      (node (ref "R35") (pin "2") (pinfunction "2_2") (pintype "passive"))
    )
    (net (code "172") (name "~{EMA2}") (class "Default")
      (node (ref "E27") (pin "13") (pinfunction "I_13") (pintype "input"))
      (node (ref "J1") (pin "32") (pinfunction "32_32") (pintype "passive"))
      (node (ref "R36") (pin "2") (pinfunction "2_2") (pintype "passive"))
    )
    (net (code "173") (name "~{EMODE}") (class "Default")
      (node (ref "E1") (pin "6") (pinfunction "MOD_6") (pintype "input"))
      (node (ref "E16") (pin "8") (pinfunction "~{Q}_8") (pintype "output"))
      (node (ref "E2") (pin "6") (pinfunction "MOD_6") (pintype "input"))
      (node (ref "E22") (pin "6") (pinfunction "I1_6") (pintype "input"))
      (node (ref "E3") (pin "6") (pinfunction "MOD_6") (pintype "input"))
    )
    (net (code "174") (name "~{EXTPUL}") (class "Default")
      (node (ref "J4") (pin "9") (pinfunction "9_9") (pintype "passive"))
    )
    (net (code "175") (name "~{FUN}") (class "Default")
      (node (ref "E24") (pin "3") (pinfunction "I_3") (pintype "input"))
      (node (ref "E25") (pin "11") (pinfunction "I2_11") (pintype "input"))
      (node (ref "E25") (pin "2") (pinfunction "I1_2") (pintype "input"))
      (node (ref "J4") (pin "15") (pinfunction "15_15") (pintype "passive"))
    )
    (net (code "176") (name "~{GATEENT}") (class "Default")
      (node (ref "E10") (pin "1") (pinfunction "G_1") (pintype "input"))
      (node (ref "E11") (pin "1") (pinfunction "G_1") (pintype "input"))
      (node (ref "E21") (pin "6") (pinfunction "O_6") (pintype "output"))
      (node (ref "E30") (pin "5") (pinfunction "I1_5") (pintype "input"))
      (node (ref "E9") (pin "1") (pinfunction "G_1") (pintype "input"))
    )
    (net (code "177") (name "~{GATESR}") (class "Default")
      (node (ref "E10") (pin "19") (pinfunction "G_19") (pintype "input"))
      (node (ref "E11") (pin "19") (pinfunction "G_19") (pintype "input"))
      (node (ref "E32") (pin "11") (pinfunction "O_11") (pintype "output"))
      (node (ref "E9") (pin "19") (pinfunction "G_19") (pintype "input"))
    )
    (net (code "178") (name "~{IND1}") (class "Default")
      (node (ref "E28") (pin "7") (pinfunction "1Y3_7") (pintype "tri_state"))
      (node (ref "E34") (pin "3") (pinfunction "1Y1_3") (pintype "tri_state"))
      (node (ref "J2") (pin "8") (pinfunction "8_8") (pintype "passive"))
    )
    (net (code "179") (name "~{IND2}") (class "Default")
      (node (ref "E34") (pin "5") (pinfunction "1Y2_5") (pintype "tri_state"))
      (node (ref "J2") (pin "4") (pinfunction "4_4") (pintype "passive"))
    )
    (net (code "180") (name "~{INIT}") (class "Default")
      (node (ref "E31") (pin "9") (pinfunction "1Y4_9") (pintype "tri_state"))
      (node (ref "J2") (pin "34") (pinfunction "34_34") (pintype "passive"))
    )
    (net (code "181") (name "~{KEY-F}") (class "Default")
      (node (ref "E26") (pin "13") (pinfunction "C12_13") (pintype "input"))
      (node (ref "E26") (pin "4") (pinfunction "C34_4") (pintype "input"))
      (node (ref "E27") (pin "5") (pinfunction "I_5") (pintype "input"))
      (node (ref "J4") (pin "3") (pinfunction "3_3") (pintype "passive"))
    )
    (net (code "182") (name "~{KEYCNTL}") (class "Default")
      (node (ref "E31") (pin "13") (pinfunction "2Y2_13") (pintype "tri_state"))
      (node (ref "J2") (pin "10") (pinfunction "10_10") (pintype "passive"))
    )
    (net (code "183") (name "~{KEYSTB}") (class "Default")
      (node (ref "E16") (pin "11") (pinfunction "CLK_11") (pintype "input"))
      (node (ref "E21") (pin "2") (pinfunction "I1_2") (pintype "input"))
      (node (ref "E24") (pin "2") (pinfunction "O_2") (pintype "output"))
      (node (ref "E31") (pin "1") (pinfunction "1G_1") (pintype "input"))
      (node (ref "E33") (pin "11") (pinfunction "I0_11") (pintype "input"))
      (node (ref "E33") (pin "9") (pinfunction "I1_9") (pintype "input"))
    )
    (net (code "184") (name "~{KFUN0}") (class "Default")
      (node (ref "E26") (pin "2") (pinfunction "D1_2") (pintype "input"))
      (node (ref "E3") (pin "1") (pinfunction "SER_1") (pintype "input"))
      (node (ref "E3") (pin "2") (pinfunction "A_2") (pintype "input"))
      (node (ref "J3") (pin "3") (pinfunction "3_3") (pintype "passive"))
    )
    (net (code "185") (name "~{KFUN1}") (class "Default")
      (node (ref "E2") (pin "1") (pinfunction "SER_1") (pintype "input"))
      (node (ref "E2") (pin "2") (pinfunction "A_2") (pintype "input"))
      (node (ref "E26") (pin "3") (pinfunction "D2_3") (pintype "input"))
      (node (ref "J3") (pin "2") (pinfunction "2_2") (pintype "passive"))
    )
    (net (code "186") (name "~{KFUN2}") (class "Default")
      (node (ref "E1") (pin "1") (pinfunction "SER_1") (pintype "input"))
      (node (ref "E1") (pin "2") (pinfunction "A_2") (pintype "input"))
      (node (ref "E26") (pin "6") (pinfunction "D3_6") (pintype "input"))
      (node (ref "J3") (pin "1") (pinfunction "1_1") (pintype "passive"))
    )
    (net (code "187") (name "~{LAENAB}") (class "Default")
      (node (ref "E23") (pin "2") (pinfunction "O_2") (pintype "open_collector"))
      (node (ref "J2") (pin "22") (pinfunction "22_22") (pintype "passive"))
    )
    (net (code "188") (name "~{MAEN}") (class "Default")
      (node (ref "E23") (pin "8") (pinfunction "O_8") (pintype "open_collector"))
      (node (ref "J2") (pin "32") (pinfunction "32_32") (pintype "passive"))
    )
    (net (code "189") (name "~{MALC}") (class "Default")
      (node (ref "E28") (pin "11") (pinfunction "2Y1_11") (pintype "tri_state"))
      (node (ref "J2") (pin "36") (pinfunction "36_36") (pintype "passive"))
    )
    (net (code "190") (name "~{MCLOCK}") (class "Default")
      (node (ref "E33") (pin "2") (pinfunction "I0_2") (pintype "input"))
      (node (ref "J4") (pin "1") (pinfunction "1_1") (pintype "passive"))
    )
    (net (code "191") (name "~{MD}") (class "Default")
      (node (ref "E34") (pin "7") (pinfunction "1Y3_7") (pintype "tri_state"))
      (node (ref "J2") (pin "18") (pinfunction "18_18") (pintype "passive"))
    )
    (net (code "192") (name "~{MEMSTART}") (class "Default")
      (node (ref "E31") (pin "3") (pinfunction "1Y1_3") (pintype "tri_state"))
      (node (ref "E31") (pin "5") (pinfunction "1Y2_5") (pintype "tri_state"))
      (node (ref "J2") (pin "26") (pinfunction "26_26") (pintype "passive"))
    )
    (net (code "193") (name "~{MH0}") (class "Default")
      (node (ref "E20") (pin "12") (pinfunction "D_12") (pintype "input"))
      (node (ref "E20") (pin "8") (pinfunction "~{Q}_8") (pintype "output"))
      (node (ref "E21") (pin "9") (pinfunction "I0_9") (pintype "input"))
      (node (ref "E8") (pin "2") (pinfunction "I1_2") (pintype "input"))
      (node (ref "E8") (pin "9") (pinfunction "I0_9") (pintype "input"))
    )
    (net (code "194") (name "~{MSIRDIS}") (class "Default")
      (node (ref "E31") (pin "11") (pinfunction "2Y1_11") (pintype "tri_state"))
      (node (ref "J2") (pin "2") (pinfunction "2_2") (pintype "passive"))
    )
    (net (code "195") (name "~{PANLOCK}") (class "Default")
      (node (ref "E24") (pin "13") (pinfunction "I_13") (pintype "input"))
      (node (ref "J2") (pin "6") (pinfunction "6_6") (pintype "passive"))
      (node (ref "R31") (pin "2") (pinfunction "2_2") (pintype "passive"))
    )
    (net (code "196") (name "~{PULSELOADADD}") (class "Default")
      (node (ref "E31") (pin "7") (pinfunction "1Y3_7") (pintype "tri_state"))
      (node (ref "J2") (pin "40") (pinfunction "40_40") (pintype "passive"))
    )
    (net (code "197") (name "~{RUN}") (class "Default")
      (node (ref "E24") (pin "5") (pinfunction "I_5") (pintype "input"))
      (node (ref "J1") (pin "18") (pinfunction "18_18") (pintype "passive"))
      (node (ref "R28") (pin "1") (pinfunction "1_1") (pintype "passive"))
    )
    (net (code "198") (name "~{SHLT}") (class "Default")
      (node (ref "E27") (pin "1") (pinfunction "I_1") (pintype "input"))
      (node (ref "J3") (pin "5") (pinfunction "5_5") (pintype "passive"))
    )
    (net (code "199") (name "~{SINGSTEP}") (class "Default")
      (node (ref "E28") (pin "13") (pinfunction "2Y2_13") (pintype "tri_state"))
      (node (ref "J2") (pin "14") (pinfunction "14_14") (pintype "passive"))
    )
    (net (code "200") (name "~{SRDATA}") (class "Default")
      (node (ref "E32") (pin "13") (pinfunction "I1_13") (pintype "input"))
      (node (ref "E8") (pin "1") (pinfunction "I0_1") (pintype "input"))
      (node (ref "J2") (pin "30") (pinfunction "30_30") (pintype "passive"))
      (node (ref "R29") (pin "2") (pinfunction "2_2") (pintype "passive"))
      (node (ref "R30") (pin "1") (pinfunction "1_1") (pintype "passive"))
    )
    (net (code "201") (name "~{STATE}") (class "Default")
      (node (ref "E34") (pin "11") (pinfunction "2Y1_11") (pintype "tri_state"))
      (node (ref "J2") (pin "38") (pinfunction "38_38") (pintype "passive"))
    )
    (net (code "202") (name "~{STHIS}") (class "Default")
      (node (ref "E20") (pin "2") (pinfunction "D_2") (pintype "input"))
      (node (ref "J3") (pin "4") (pinfunction "4_4") (pintype "passive"))
    )
    (net (code "203") (name "~{TS1}") (class "Default")
      (node (ref "E20") (pin "3") (pinfunction "CLK_3") (pintype "input"))
      (node (ref "E21") (pin "10") (pinfunction "I1_10") (pintype "input"))
      (node (ref "E24") (pin "9") (pinfunction "I_9") (pintype "input"))
      (node (ref "J1") (pin "26") (pinfunction "26_26") (pintype "passive"))
      (node (ref "R26") (pin "2") (pinfunction "2_2") (pintype "passive"))
      (node (ref "R27") (pin "1") (pinfunction "1_1") (pintype "passive"))
    )
  )
)
